# electron_v020.net
KiCad netlist of a schematic drawn in EAGLE
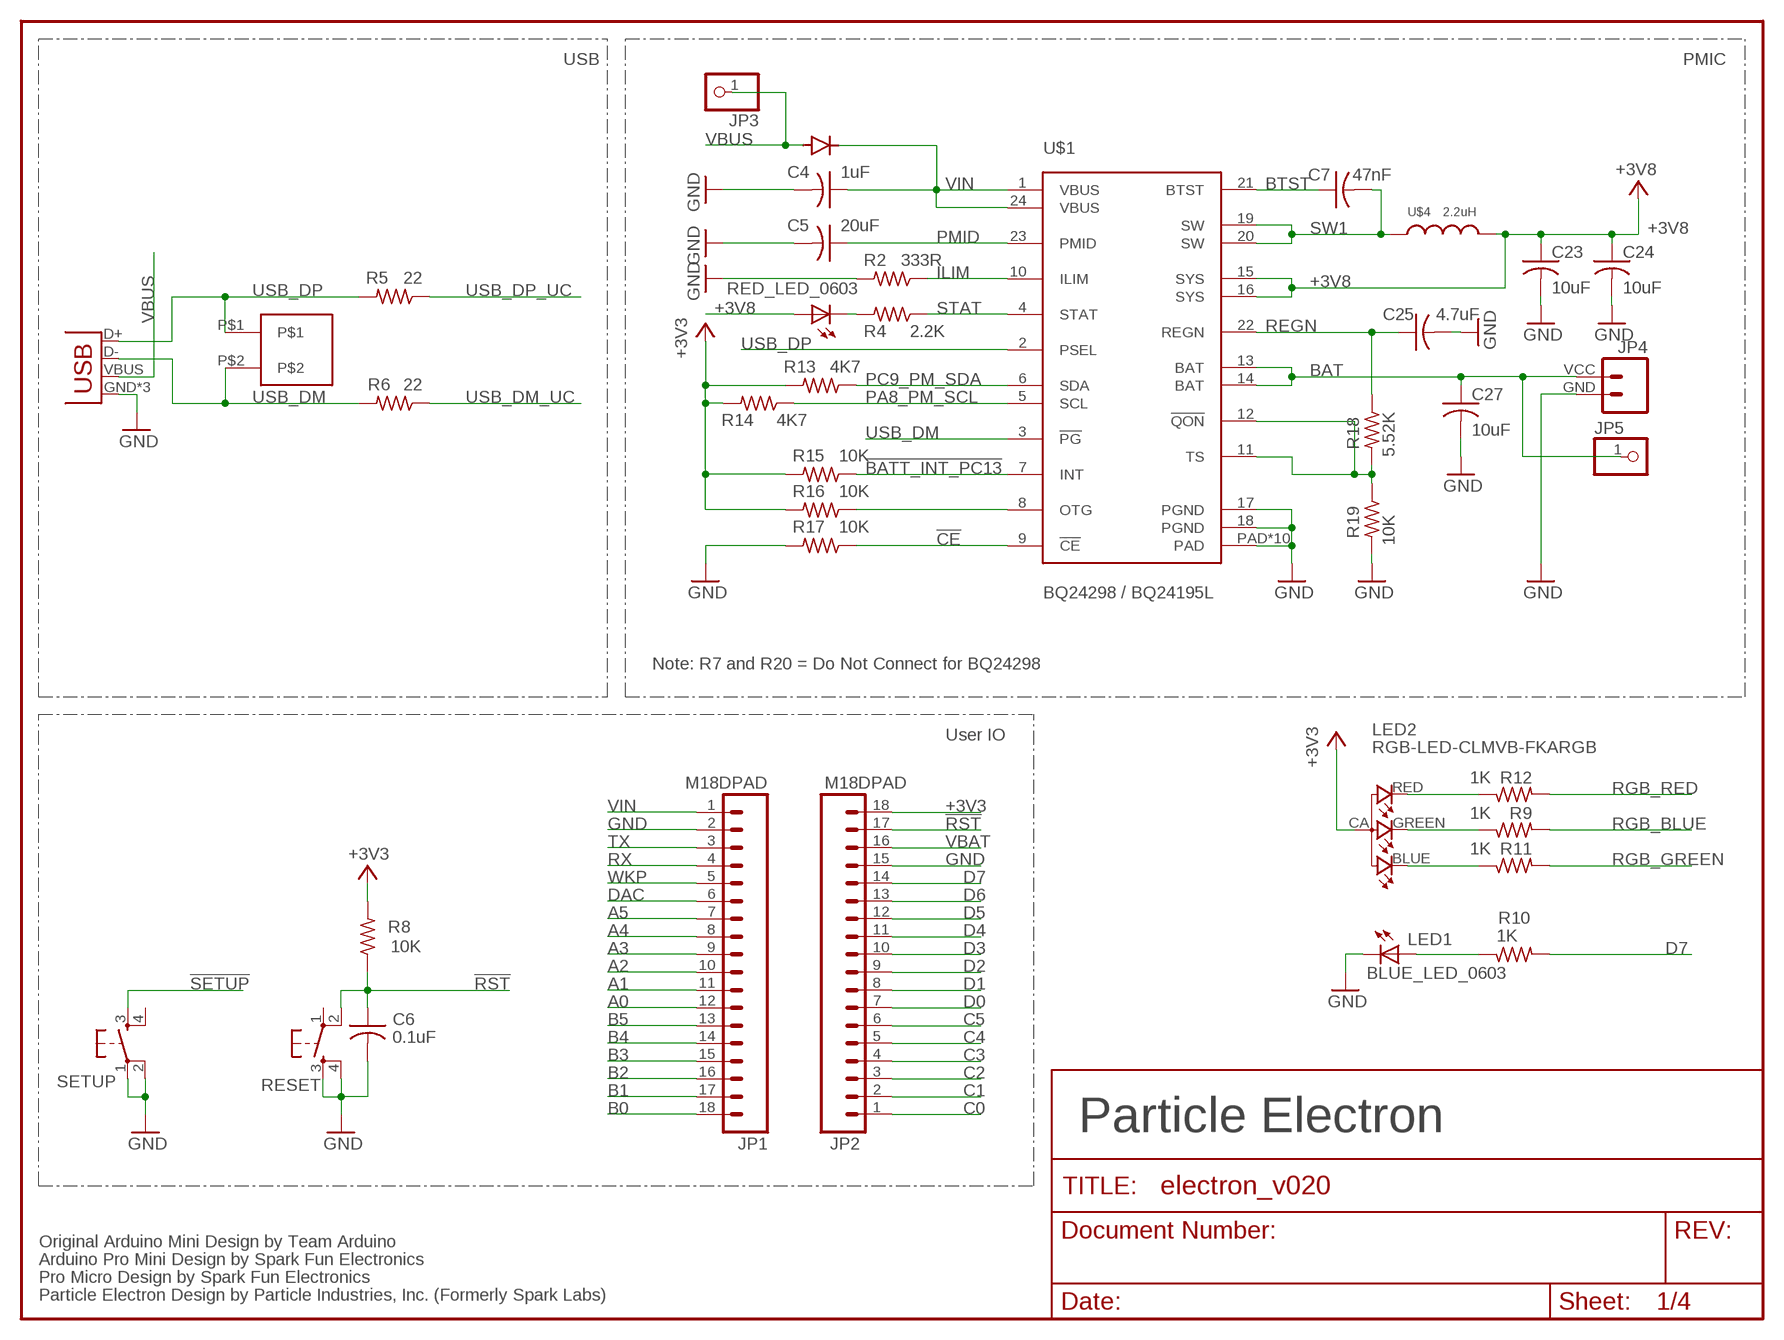
[diagram p0: schematic, sheet 1]
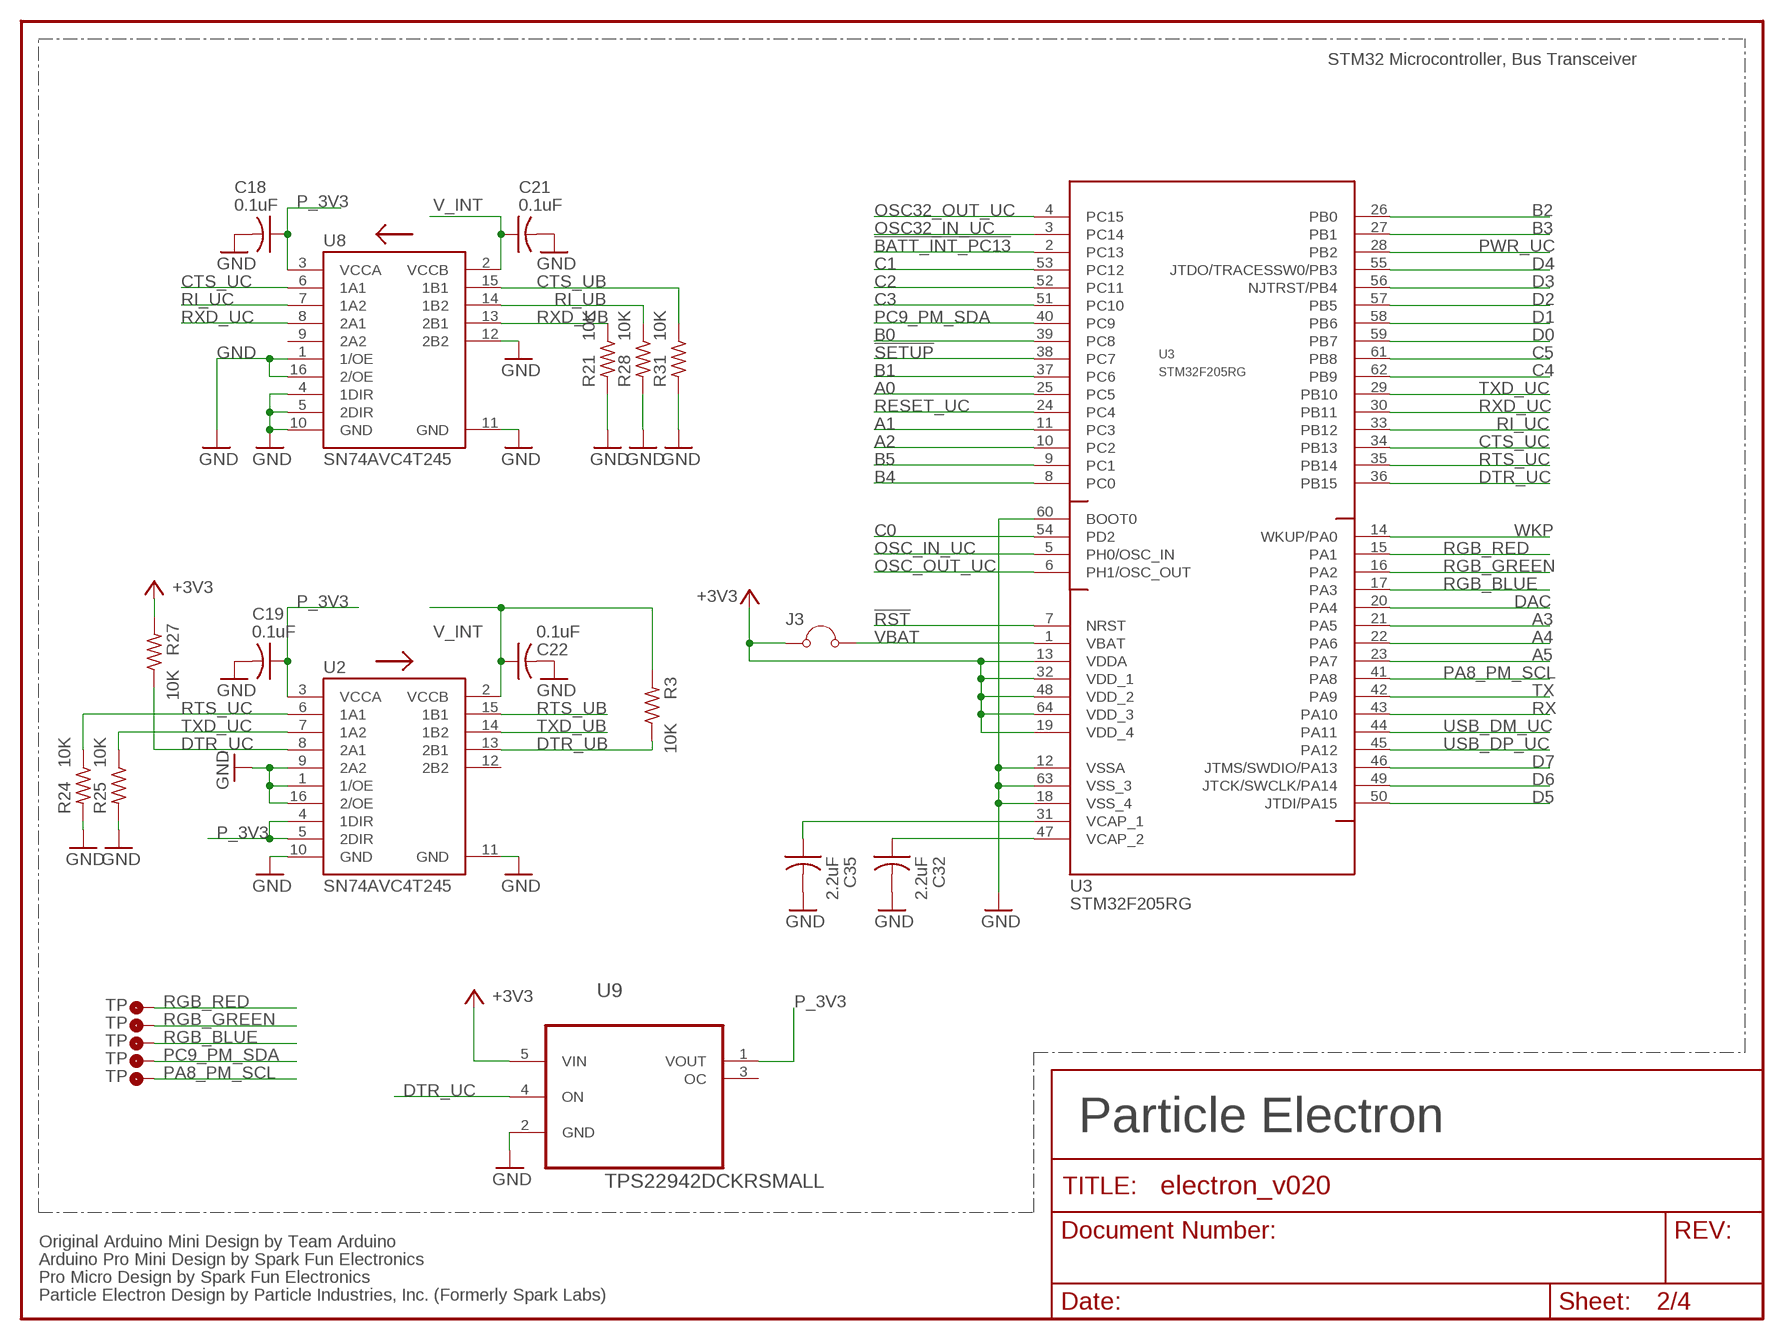
[diagram p1: schematic, sheet 2]
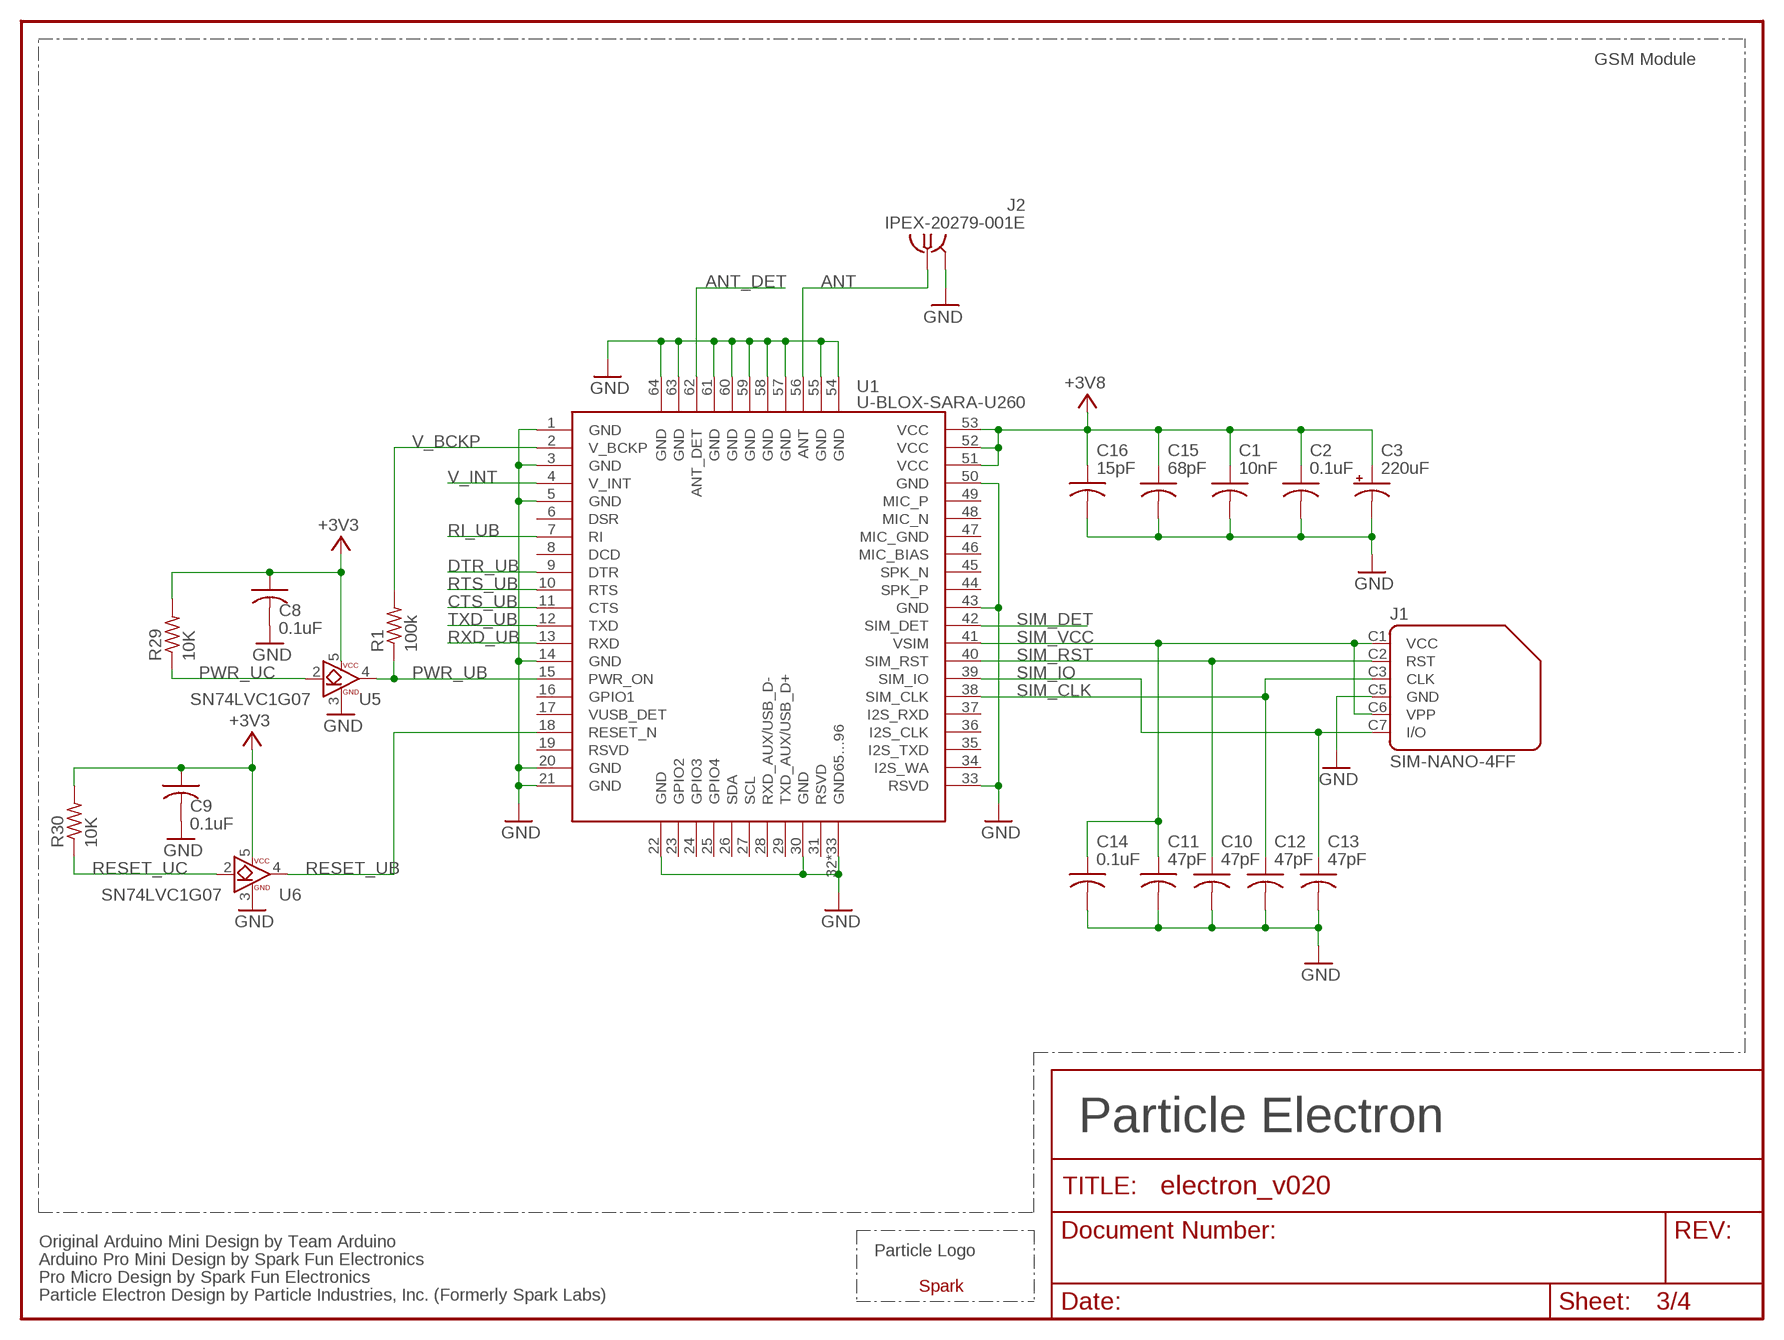
[diagram p2: schematic, sheet 3]
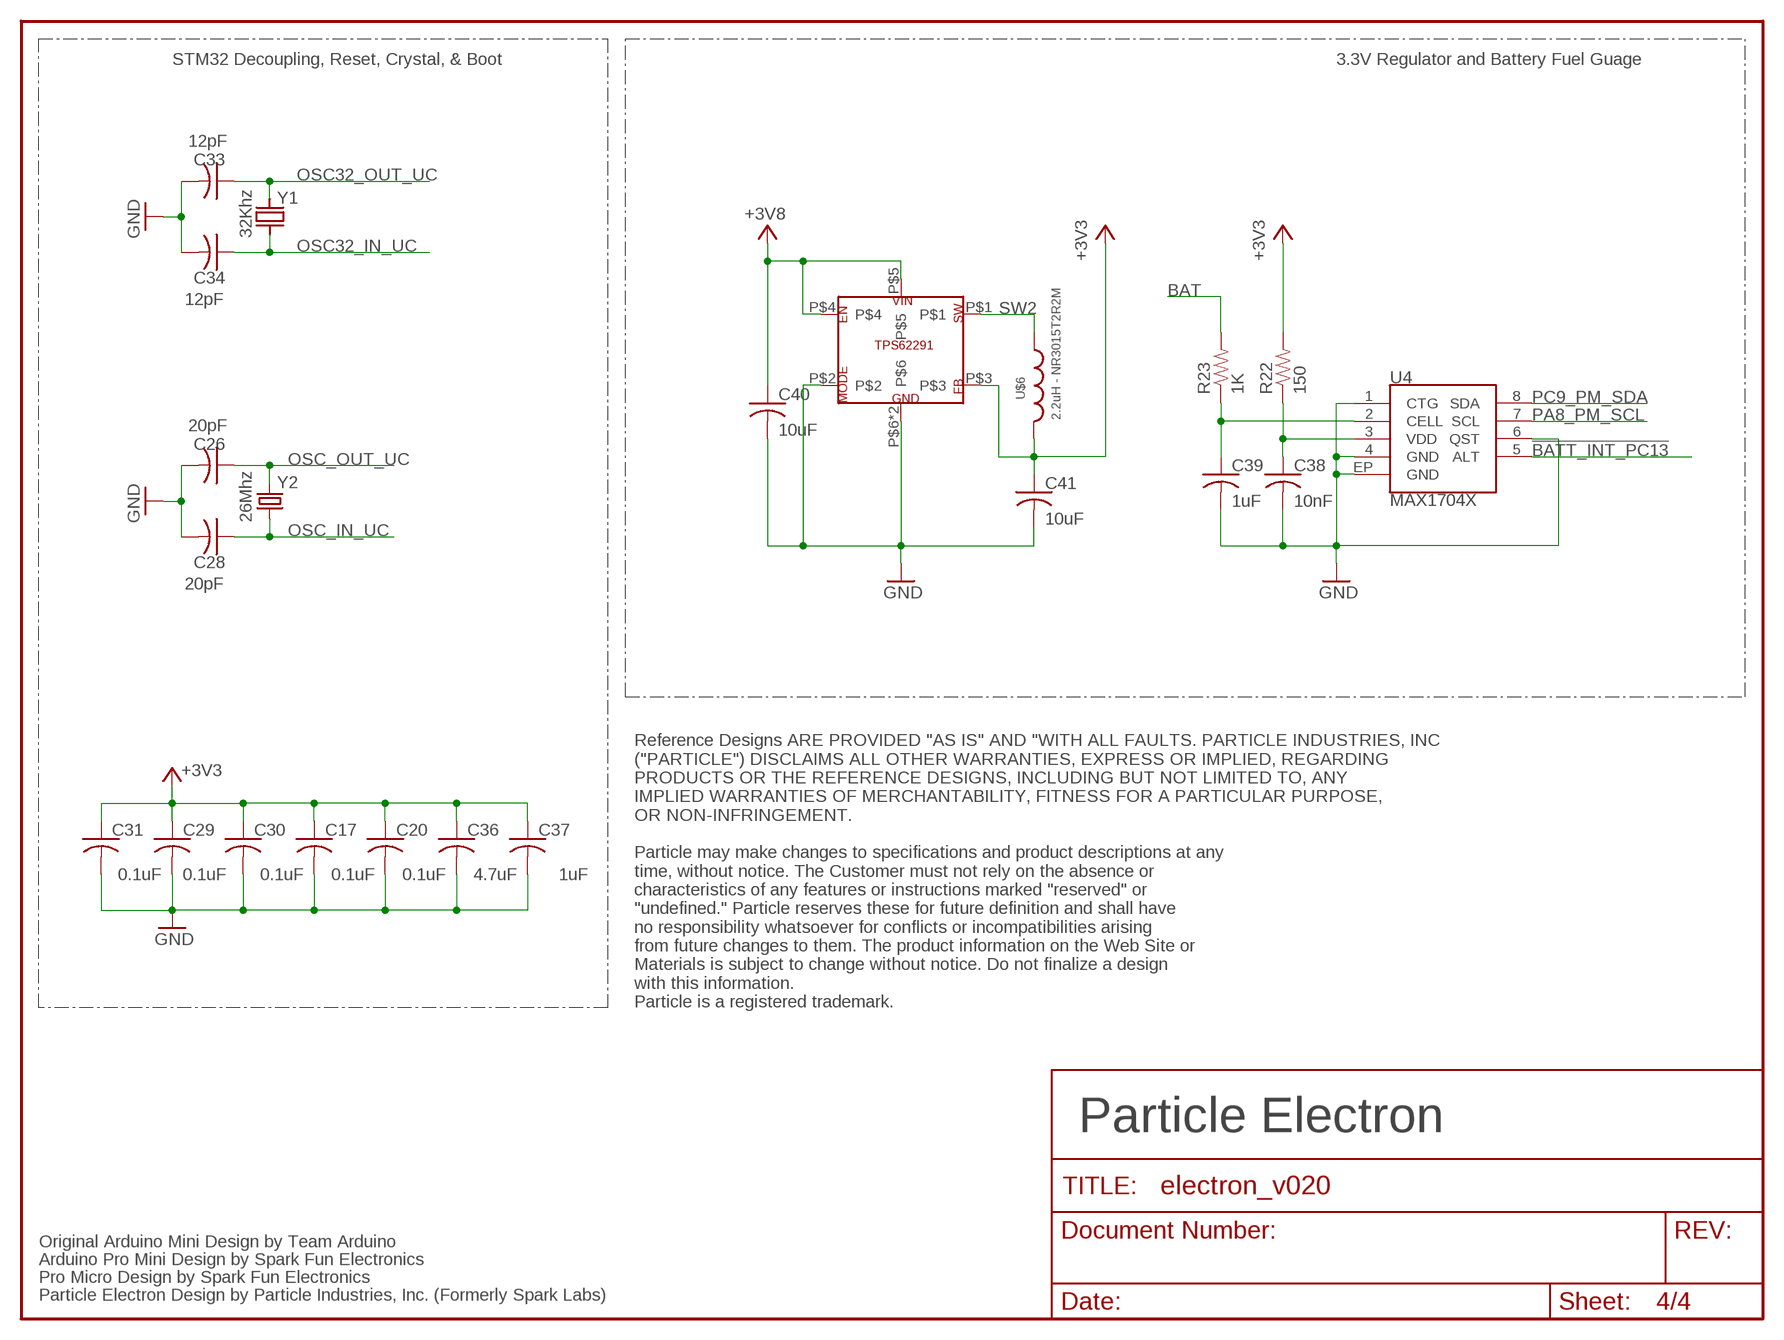
[diagram p3: schematic, sheet 4]

(export (version "E")
  (design (tool "Eeschema 10.0.6"))
  (components
    (comp (ref "C1")
      (value "10nF")
      (footprint "eagle-import:C0402_B")
      (libsource (lib "eagle-import") (part "C-US"))
    )
    (comp (ref "C2")
      (value "0.1uF")
      (footprint "eagle-import:C0402_B")
      (libsource (lib "eagle-import") (part "C-US"))
    )
    (comp (ref "C3")
      (value "220uF")
      (footprint "eagle-import:C_6032-28R")
      (libsource (lib "eagle-import") (part "CPOL-USC/6032-28R"))
    )
    (comp (ref "C8")
      (value "0.1uF")
      (footprint "eagle-import:C0402_B")
      (libsource (lib "eagle-import") (part "C-US"))
    )
    (comp (ref "C9")
      (value "0.1uF")
      (footprint "eagle-import:C0402_B")
      (libsource (lib "eagle-import") (part "C-US"))
    )
    (comp (ref "C10")
      (value "47pF")
      (footprint "eagle-import:C0402_B")
      (libsource (lib "eagle-import") (part "C-US"))
    )
    (comp (ref "C11")
      (value "47pF")
      (footprint "eagle-import:C0402_B")
      (libsource (lib "eagle-import") (part "C-US"))
    )
    (comp (ref "C12")
      (value "47pF")
      (footprint "eagle-import:C0402_B")
      (libsource (lib "eagle-import") (part "C-US"))
    )
    (comp (ref "C13")
      (value "47pF")
      (footprint "eagle-import:C0402_B")
      (libsource (lib "eagle-import") (part "C-US"))
    )
    (comp (ref "C14")
      (value "0.1uF")
      (footprint "eagle-import:C0402_B")
      (libsource (lib "eagle-import") (part "C-US"))
    )
    (comp (ref "C15")
      (value "68pF")
      (footprint "eagle-import:C0402_B")
      (libsource (lib "eagle-import") (part "C-US"))
    )
    (comp (ref "C16")
      (value "15pF")
      (footprint "eagle-import:C0402_B")
      (libsource (lib "eagle-import") (part "C-US"))
    )
    (comp (ref "J1")
      (value "SIM-NANO-4FF")
      (footprint "eagle-import:GCT-SIM8100")
      (libsource (lib "eagle-import") (part "SIM-NANO-4FF"))
    )
    (comp (ref "J2")
      (value "IPEX-20279-001E")
      (footprint "eagle-import:IPEX-20279-001E")
      (libsource (lib "eagle-import") (part "IPEX-20279-001E"))
    )
    (comp (ref "R1")
      (value "100k")
      (footprint "eagle-import:R0402_B")
      (libsource (lib "eagle-import") (part "R-US_"))
    )
    (comp (ref "R29")
      (value "10K")
      (footprint "eagle-import:R0402_B")
      (libsource (lib "eagle-import") (part "R-US_"))
    )
    (comp (ref "R30")
      (value "10K")
      (footprint "eagle-import:R0402_B")
      (libsource (lib "eagle-import") (part "R-US_"))
    )
    (comp (ref "U$2")
      (value "SPARK_LOGO2")
      (footprint "eagle-import:SPARK_LOGO2")
      (libsource (lib "eagle-import") (part "SPARK_LOGO2"))
    )
    (comp (ref "U1")
      (value "U-BLOX-SARA-U260")
      (footprint "eagle-import:U-BLOX-SARA-U2")
      (libsource (lib "eagle-import") (part "U-BLOX-SARA-U260"))
    )
    (comp (ref "U5")
      (value "SN74LVC1G07")
      (footprint "eagle-import:SC-70-5")
      (libsource (lib "eagle-import") (part "SN74LVC1G07"))
    )
    (comp (ref "U6")
      (value "SN74LVC1G07")
      (footprint "eagle-import:SC-70-5")
      (libsource (lib "eagle-import") (part "SN74LVC1G07"))
    )
    (comp (ref "BLUE_LED_0603")
      (value "LEDNOSILK")
      (footprint "eagle-import:LED-0603-NS")
      (libsource (lib "eagle-import") (part "LEDNOSILK"))
    )
    (comp (ref "C4")
      (value "1uF")
      (footprint "eagle-import:C0603_B")
      (libsource (lib "eagle-import") (part "C-US0603"))
    )
    (comp (ref "C5")
      (value "20uF")
      (footprint "eagle-import:C0603_B")
      (libsource (lib "eagle-import") (part "C-US0603"))
    )
    (comp (ref "C6")
      (value "0.1uF")
      (footprint "eagle-import:C0402_B")
      (libsource (lib "eagle-import") (part "C-US"))
    )
    (comp (ref "C7")
      (value "47nF")
      (footprint "eagle-import:C0402_B")
      (libsource (lib "eagle-import") (part "C-US"))
    )
    (comp (ref "C23")
      (value "10uF")
      (footprint "eagle-import:C0603_B")
      (libsource (lib "eagle-import") (part "C-US0603"))
    )
    (comp (ref "C24")
      (value "10uF")
      (footprint "eagle-import:C0603_B")
      (libsource (lib "eagle-import") (part "C-US0603"))
    )
    (comp (ref "C25")
      (value "4.7uF")
      (footprint "eagle-import:C0603_B")
      (libsource (lib "eagle-import") (part "C-US0603"))
    )
    (comp (ref "C27")
      (value "10uF")
      (footprint "eagle-import:C0603_B")
      (libsource (lib "eagle-import") (part "C-US0603"))
    )
    (comp (ref "JP1")
      (value "M18DPAD")
      (footprint "eagle-import:1X18-D-PADS")
      (libsource (lib "eagle-import") (part "M18DPAD"))
    )
    (comp (ref "JP2")
      (value "M18DPAD")
      (footprint "eagle-import:1X18-D-PADS")
      (libsource (lib "eagle-import") (part "M18DPAD"))
    )
    (comp (ref "JP3")
      (value "PINHD-1X1NOSILK")
      (footprint "eagle-import:1X01_NO_SILK")
      (libsource (lib "eagle-import") (part "PINHD-1X1NOSILK"))
    )
    (comp (ref "JP4")
      (value "M024UCON-15767")
      (footprint "eagle-import:JST-2-SMD-VERT")
      (libsource (lib "eagle-import") (part "M024UCON-15767"))
    )
    (comp (ref "JP5")
      (value "PINHD-1X1NOSILK")
      (footprint "eagle-import:1X01_NO_SILK")
      (libsource (lib "eagle-import") (part "PINHD-1X1NOSILK"))
    )
    (comp (ref "LED2")
      (value "RGB-LED-CLMVB-FKARGB")
      (footprint "eagle-import:PLCC4-2MM-RGB")
      (libsource (lib "eagle-import") (part "RGB-LED-CLMVB-FKARGB"))
    )
    (comp (ref "R2")
      (value "333R")
      (footprint "eagle-import:R0402_B")
      (libsource (lib "eagle-import") (part "R-US_"))
    )
    (comp (ref "R4")
      (value "2.2K")
      (footprint "eagle-import:R0402_B")
      (libsource (lib "eagle-import") (part "R-US_"))
    )
    (comp (ref "R5")
      (value "22")
      (footprint "eagle-import:R0402_B")
      (libsource (lib "eagle-import") (part "R-US_"))
    )
    (comp (ref "R6")
      (value "22")
      (footprint "eagle-import:R0402_B")
      (libsource (lib "eagle-import") (part "R-US_"))
    )
    (comp (ref "R8")
      (value "10K")
      (footprint "eagle-import:R0402_B")
      (libsource (lib "eagle-import") (part "R-US_"))
    )
    (comp (ref "R9")
      (value "1K")
      (footprint "eagle-import:R0402_B")
      (libsource (lib "eagle-import") (part "R-US_"))
    )
    (comp (ref "R10")
      (value "1K")
      (footprint "eagle-import:R0402_B")
      (libsource (lib "eagle-import") (part "R-US_"))
    )
    (comp (ref "R11")
      (value "1K")
      (footprint "eagle-import:R0402_B")
      (libsource (lib "eagle-import") (part "R-US_"))
    )
    (comp (ref "R12")
      (value "1K")
      (footprint "eagle-import:R0402_B")
      (libsource (lib "eagle-import") (part "R-US_"))
    )
    (comp (ref "R13")
      (value "4K7")
      (footprint "eagle-import:R0402_B")
      (libsource (lib "eagle-import") (part "R-US_"))
    )
    (comp (ref "R14")
      (value "4K7")
      (footprint "eagle-import:R0402_B")
      (libsource (lib "eagle-import") (part "R-US_"))
    )
    (comp (ref "R15")
      (value "10K")
      (footprint "eagle-import:R0402_B")
      (libsource (lib "eagle-import") (part "R-US_"))
    )
    (comp (ref "R16")
      (value "10K")
      (footprint "eagle-import:R0402_B")
      (libsource (lib "eagle-import") (part "R-US_"))
    )
    (comp (ref "R17")
      (value "10K")
      (footprint "eagle-import:R0402_B")
      (libsource (lib "eagle-import") (part "R-US_"))
    )
    (comp (ref "R18")
      (value "5.52K")
      (footprint "eagle-import:R0402_B")
      (libsource (lib "eagle-import") (part "R-US_"))
    )
    (comp (ref "R19")
      (value "10K")
      (footprint "eagle-import:R0402_B")
      (libsource (lib "eagle-import") (part "R-US_"))
    )
    (comp (ref "RED_LED_0603")
      (value "LED0603")
      (footprint "eagle-import:LED-0603")
      (libsource (lib "eagle-import") (part "LED0603"))
    )
    (comp (ref "RESET")
      (value "KMR211GLFS")
      (footprint "eagle-import:TACTILE_SWITCH_SMD")
      (libsource (lib "eagle-import") (part "TAC_SWITCHSMD"))
    )
    (comp (ref "SETUP")
      (value "KMR211GLFS")
      (footprint "eagle-import:TACTILE_SWITCH_SMD")
      (libsource (lib "eagle-import") (part "TAC_SWITCHSMD"))
    )
    (comp (ref "U$1")
      (value "BQ24298 / BQ24195L")
      (footprint "eagle-import:QFN24")
      (libsource (lib "eagle-import") (part "BQ24298RTWR"))
    )
    (comp (ref "U$3")
      (value "DIODE_NT")
      (footprint "eagle-import:DIODE-DO-220AA_NT(SMP)")
      (libsource (lib "eagle-import") (part "DIODE_NT"))
    )
    (comp (ref "U$4")
      (value "2.2uH")
      (footprint "eagle-import:4020TYPE_NT")
      (libsource (lib "eagle-import") (part "INDUCTOR_NT"))
    )
    (comp (ref "U$7")
      (value "M02_0.05_HEADER")
      (footprint "eagle-import:M02_0.05_HEADER")
      (libsource (lib "eagle-import") (part "M02_0.05_HEADER"))
    )
    (comp (ref "X1")
      (value "USB-MICROB")
      (footprint "eagle-import:USB-MICROB-SLOT-HOLE")
      (libsource (lib "eagle-import") (part "USBUSB-MICROB-SLOT-HOLE"))
    )
    (comp (ref "C17")
      (value "0.1uF")
      (footprint "eagle-import:C0402_B")
      (libsource (lib "eagle-import") (part "C-US"))
    )
    (comp (ref "C20")
      (value "0.1uF")
      (footprint "eagle-import:C0402_B")
      (libsource (lib "eagle-import") (part "C-US"))
    )
    (comp (ref "C26")
      (value "20pF")
      (footprint "eagle-import:C0402_B")
      (libsource (lib "eagle-import") (part "C-US"))
    )
    (comp (ref "C28")
      (value "20pF")
      (footprint "eagle-import:C0402_B")
      (libsource (lib "eagle-import") (part "C-US"))
    )
    (comp (ref "C29")
      (value "0.1uF")
      (footprint "eagle-import:C0402_B")
      (libsource (lib "eagle-import") (part "C-US"))
    )
    (comp (ref "C30")
      (value "0.1uF")
      (footprint "eagle-import:C0402_B")
      (libsource (lib "eagle-import") (part "C-US"))
    )
    (comp (ref "C31")
      (value "0.1uF")
      (footprint "eagle-import:C0402_B")
      (libsource (lib "eagle-import") (part "C-US"))
    )
    (comp (ref "C33")
      (value "12pF")
      (footprint "eagle-import:C0402_B")
      (libsource (lib "eagle-import") (part "C-US"))
    )
    (comp (ref "C34")
      (value "12pF")
      (footprint "eagle-import:C0402_B")
      (libsource (lib "eagle-import") (part "C-US"))
    )
    (comp (ref "C36")
      (value "4.7uF")
      (footprint "eagle-import:C0402_B")
      (libsource (lib "eagle-import") (part "C-US"))
    )
    (comp (ref "C37")
      (value "1uF")
      (footprint "eagle-import:C0402_B")
      (libsource (lib "eagle-import") (part "C-US"))
    )
    (comp (ref "C38")
      (value "10nF")
      (footprint "eagle-import:C0402_B")
      (libsource (lib "eagle-import") (part "C-US"))
    )
    (comp (ref "C39")
      (value "1uF")
      (footprint "eagle-import:C0402_B")
      (libsource (lib "eagle-import") (part "C-US"))
    )
    (comp (ref "C40")
      (value "10uF")
      (footprint "eagle-import:C0603_B")
      (libsource (lib "eagle-import") (part "C-US0603"))
    )
    (comp (ref "C41")
      (value "10uF")
      (footprint "eagle-import:C0603_B")
      (libsource (lib "eagle-import") (part "C-US0603"))
    )
    (comp (ref "R22")
      (value "150")
      (footprint "eagle-import:0603-RES")
      (libsource (lib "eagle-import") (part "RESISTOR0603-RES"))
    )
    (comp (ref "R23")
      (value "1K")
      (footprint "eagle-import:0603-RES")
      (libsource (lib "eagle-import") (part "RESISTOR0603-RES"))
    )
    (comp (ref "U$5")
      (value "TPS62291DRV")
      (footprint "eagle-import:S-PWSON-N6")
      (libsource (lib "eagle-import") (part "TPS62291DRV"))
    )
    (comp (ref "U$6")
      (value "2.2uH - NR3015T2R2M")
      (footprint "eagle-import:INDUCTOR-NR3015")
      (libsource (lib "eagle-import") (part "INDUCTORB"))
    )
    (comp (ref "U4")
      (value "MAX1704X")
      (footprint "eagle-import:TDFN-8")
      (libsource (lib "eagle-import") (part "MAX1704X"))
    )
    (comp (ref "Y1")
      (value "32Khz")
      (footprint "eagle-import:FC135")
      (libsource (lib "eagle-import") (part "Q_FC135"))
    )
    (comp (ref "Y2")
      (value "26Mhz")
      (footprint "eagle-import:CRYSTAL-SMD-5X3")
      (libsource (lib "eagle-import") (part "CRYSTAL5X3"))
    )
    (comp (ref "C18")
      (value "0.1uF")
      (footprint "eagle-import:C0402_B")
      (libsource (lib "eagle-import") (part "C-US"))
    )
    (comp (ref "C19")
      (value "0.1uF")
      (footprint "eagle-import:C0402_B")
      (libsource (lib "eagle-import") (part "C-US"))
    )
    (comp (ref "C21")
      (value "0.1uF")
      (footprint "eagle-import:C0402_B")
      (libsource (lib "eagle-import") (part "C-US"))
    )
    (comp (ref "C22")
      (value "0.1uF")
      (footprint "eagle-import:C0402_B")
      (libsource (lib "eagle-import") (part "C-US"))
    )
    (comp (ref "C32")
      (value "2.2uF")
      (footprint "eagle-import:C0402_B")
      (libsource (lib "eagle-import") (part "C-US"))
    )
    (comp (ref "C35")
      (value "2.2uF")
      (footprint "eagle-import:C0402_B")
      (libsource (lib "eagle-import") (part "C-US"))
    )
    (comp (ref "J3")
      (value "JUMPER_NC_SMD")
      (footprint "eagle-import:JUMPER_SMD_NC")
      (libsource (lib "eagle-import") (part "JUMPER_NC_SMD"))
    )
    (comp (ref "R3")
      (value "10K")
      (footprint "eagle-import:R0402_B")
      (libsource (lib "eagle-import") (part "R-US_"))
    )
    (comp (ref "R21")
      (value "10K")
      (footprint "eagle-import:R0402_B")
      (libsource (lib "eagle-import") (part "R-US_"))
    )
    (comp (ref "R24")
      (value "10K")
      (footprint "eagle-import:R0402_B")
      (libsource (lib "eagle-import") (part "R-US_"))
    )
    (comp (ref "R25")
      (value "10K")
      (footprint "eagle-import:R0402_B")
      (libsource (lib "eagle-import") (part "R-US_"))
    )
    (comp (ref "R27")
      (value "10K")
      (footprint "eagle-import:R0402_B")
      (libsource (lib "eagle-import") (part "R-US_"))
    )
    (comp (ref "R28")
      (value "10K")
      (footprint "eagle-import:R0402_B")
      (libsource (lib "eagle-import") (part "R-US_"))
    )
    (comp (ref "R31")
      (value "10K")
      (footprint "eagle-import:R0402_B")
      (libsource (lib "eagle-import") (part "R-US_"))
    )
    (comp (ref "U$8")
      (value "TP0")
      (footprint "eagle-import:TP30_BOT")
      (libsource (lib "eagle-import") (part "TP0"))
    )
    (comp (ref "U$9")
      (value "TP0")
      (footprint "eagle-import:TP30_BOT")
      (libsource (lib "eagle-import") (part "TP0"))
    )
    (comp (ref "U$11")
      (value "TP0")
      (footprint "eagle-import:TP30_BOT")
      (libsource (lib "eagle-import") (part "TP0"))
    )
    (comp (ref "U$12")
      (value "TP0")
      (footprint "eagle-import:TP30_BOT")
      (libsource (lib "eagle-import") (part "TP0"))
    )
    (comp (ref "U$13")
      (value "TP0")
      (footprint "eagle-import:TP30_BOT")
      (libsource (lib "eagle-import") (part "TP0"))
    )
    (comp (ref "U2")
      (value "SN74AVC4T245")
      (footprint "eagle-import:UFQFN-16")
      (libsource (lib "eagle-import") (part "SN74AVC4T245"))
    )
    (comp (ref "U3")
      (value "STM32F205RG")
      (footprint "eagle-import:LQFP64")
      (libsource (lib "eagle-import") (part "STM32F20XR"))
    )
    (comp (ref "U8")
      (value "SN74AVC4T245")
      (footprint "eagle-import:UFQFN-16")
      (libsource (lib "eagle-import") (part "SN74AVC4T245"))
    )
    (comp (ref "U9")
      (value "TPS22942DCKRSMALL")
      (footprint "eagle-import:SC70-5")
      (libsource (lib "eagle-import") (part "TPS22942DCKRSMALL"))
    )
  )
  (nets
    (net (code "1") (name "+3V3") (class "Default")
      (node (ref "C17") (pin "1") (pinfunction "1_1") (pintype "passive"))
      (node (ref "C20") (pin "1") (pinfunction "1_1") (pintype "passive"))
      (node (ref "C29") (pin "1") (pinfunction "1_1") (pintype "passive"))
      (node (ref "C30") (pin "1") (pinfunction "1_1") (pintype "passive"))
      (node (ref "C31") (pin "1") (pinfunction "1_1") (pintype "passive"))
      (node (ref "C36") (pin "1") (pinfunction "1_1") (pintype "passive"))
      (node (ref "C37") (pin "1") (pinfunction "1_1") (pintype "passive"))
      (node (ref "C41") (pin "1") (pinfunction "1_1") (pintype "passive"))
      (node (ref "C8") (pin "1") (pinfunction "1_1") (pintype "passive"))
      (node (ref "C9") (pin "1") (pinfunction "1_1") (pintype "passive"))
      (node (ref "J3") (pin "1") (pinfunction "1_1") (pintype "bidirectional"))
      (node (ref "JP2") (pin "18") (pinfunction "18_18") (pintype "passive"))
      (node (ref "LED2") (pin "CA") (pinfunction "1_CA") (pintype "passive"))
      (node (ref "R13") (pin "2") (pinfunction "2_2") (pintype "passive"))
      (node (ref "R14") (pin "2") (pinfunction "2_2") (pintype "passive"))
      (node (ref "R15") (pin "2") (pinfunction "2_2") (pintype "passive"))
      (node (ref "R16") (pin "2") (pinfunction "2_2") (pintype "passive"))
      (node (ref "R22") (pin "2") (pinfunction "2_2") (pintype "passive"))
      (node (ref "R27") (pin "2") (pinfunction "2_2") (pintype "passive"))
      (node (ref "R29") (pin "2") (pinfunction "2_2") (pintype "passive"))
      (node (ref "R30") (pin "2") (pinfunction "2_2") (pintype "passive"))
      (node (ref "R8") (pin "2") (pinfunction "2_2") (pintype "passive"))
      (node (ref "U$5") (pin "P$3") (pinfunction "P$3_P$3") (pintype "bidirectional"))
      (node (ref "U$6") (pin "2") (pinfunction "2_2") (pintype "passive"))
      (node (ref "U3") (pin "13") (pinfunction "VDDA_13") (pintype "power_in"))
      (node (ref "U3") (pin "19") (pinfunction "VDD_4_19") (pintype "power_in"))
      (node (ref "U3") (pin "32") (pinfunction "VDD_1_32") (pintype "power_in"))
      (node (ref "U3") (pin "48") (pinfunction "VDD_2_48") (pintype "power_in"))
      (node (ref "U3") (pin "64") (pinfunction "VDD_3_64") (pintype "power_in"))
      (node (ref "U5") (pin "5") (pinfunction "VCC_5") (pintype "bidirectional"))
      (node (ref "U6") (pin "5") (pinfunction "VCC_5") (pintype "bidirectional"))
      (node (ref "U9") (pin "5") (pinfunction "VIN_5") (pintype "power_in"))
    )
    (net (code "2") (name "+3V8") (class "Default")
      (node (ref "C1") (pin "1") (pinfunction "1_1") (pintype "passive"))
      (node (ref "C15") (pin "1") (pinfunction "1_1") (pintype "passive"))
      (node (ref "C16") (pin "1") (pinfunction "1_1") (pintype "passive"))
      (node (ref "C2") (pin "1") (pinfunction "1_1") (pintype "passive"))
      (node (ref "C23") (pin "1") (pinfunction "1_1") (pintype "passive"))
      (node (ref "C24") (pin "1") (pinfunction "1_1") (pintype "passive"))
      (node (ref "C3") (pin "+") (pinfunction "+_+") (pintype "passive"))
      (node (ref "C40") (pin "1") (pinfunction "1_1") (pintype "passive"))
      (node (ref "RED_LED_0603") (pin "A") (pinfunction "A_A") (pintype "passive"))
      (node (ref "U$1") (pin "15") (pinfunction "SYS_15") (pintype "power_in"))
      (node (ref "U$1") (pin "16") (pinfunction "SYS_16") (pintype "power_in"))
      (node (ref "U$4") (pin "P$2") (pinfunction "2_P$2") (pintype "passive"))
      (node (ref "U$5") (pin "P$4") (pinfunction "P$4_P$4") (pintype "bidirectional"))
      (node (ref "U$5") (pin "P$5") (pinfunction "P$5_P$5") (pintype "bidirectional"))
      (node (ref "U1") (pin "51") (pinfunction "VCC_51") (pintype "bidirectional"))
      (node (ref "U1") (pin "52") (pinfunction "VCC_52") (pintype "bidirectional"))
      (node (ref "U1") (pin "53") (pinfunction "VCC_53") (pintype "bidirectional"))
    )
    (net (code "3") (name "A0") (class "Default")
      (node (ref "JP1") (pin "12") (pinfunction "12_12") (pintype "passive"))
      (node (ref "U3") (pin "25") (pinfunction "PC5_25") (pintype "bidirectional"))
    )
    (net (code "4") (name "A1") (class "Default")
      (node (ref "JP1") (pin "11") (pinfunction "11_11") (pintype "passive"))
      (node (ref "U3") (pin "11") (pinfunction "PC3_11") (pintype "bidirectional"))
    )
    (net (code "5") (name "A2") (class "Default")
      (node (ref "JP1") (pin "10") (pinfunction "10_10") (pintype "passive"))
      (node (ref "U3") (pin "10") (pinfunction "PC2_10") (pintype "bidirectional"))
    )
    (net (code "6") (name "A3") (class "Default")
      (node (ref "JP1") (pin "9") (pinfunction "9_9") (pintype "passive"))
      (node (ref "U3") (pin "21") (pinfunction "PA5_21") (pintype "bidirectional"))
    )
    (net (code "7") (name "A4") (class "Default")
      (node (ref "JP1") (pin "8") (pinfunction "8_8") (pintype "passive"))
      (node (ref "U3") (pin "22") (pinfunction "PA6_22") (pintype "bidirectional"))
    )
    (net (code "8") (name "A5") (class "Default")
      (node (ref "JP1") (pin "7") (pinfunction "7_7") (pintype "passive"))
      (node (ref "U3") (pin "23") (pinfunction "PA7_23") (pintype "bidirectional"))
    )
    (net (code "9") (name "ANT") (class "Default")
      (node (ref "J2") (pin "1") (pinfunction "1_1") (pintype "passive"))
      (node (ref "U1") (pin "56") (pinfunction "ANT_56") (pintype "bidirectional"))
    )
    (net (code "10") (name "ANT_DET") (class "Default")
      (node (ref "U1") (pin "62") (pinfunction "ANT_DET_62") (pintype "bidirectional"))
    )
    (net (code "11") (name "B0") (class "Default")
      (node (ref "JP1") (pin "18") (pinfunction "18_18") (pintype "passive"))
      (node (ref "U3") (pin "39") (pinfunction "PC8_39") (pintype "bidirectional"))
    )
    (net (code "12") (name "B1") (class "Default")
      (node (ref "JP1") (pin "17") (pinfunction "17_17") (pintype "passive"))
      (node (ref "U3") (pin "37") (pinfunction "PC6_37") (pintype "bidirectional"))
    )
    (net (code "13") (name "B2") (class "Default")
      (node (ref "JP1") (pin "16") (pinfunction "16_16") (pintype "passive"))
      (node (ref "U3") (pin "26") (pinfunction "PB0_26") (pintype "bidirectional"))
    )
    (net (code "14") (name "B3") (class "Default")
      (node (ref "JP1") (pin "15") (pinfunction "15_15") (pintype "passive"))
      (node (ref "U3") (pin "27") (pinfunction "PB1_27") (pintype "bidirectional"))
    )
    (net (code "15") (name "B4") (class "Default")
      (node (ref "JP1") (pin "14") (pinfunction "14_14") (pintype "passive"))
      (node (ref "U3") (pin "8") (pinfunction "PC0_8") (pintype "bidirectional"))
    )
    (net (code "16") (name "B5") (class "Default")
      (node (ref "JP1") (pin "13") (pinfunction "13_13") (pintype "passive"))
      (node (ref "U3") (pin "9") (pinfunction "PC1_9") (pintype "bidirectional"))
    )
    (net (code "17") (name "BAT") (class "Default")
      (node (ref "C27") (pin "1") (pinfunction "1_1") (pintype "passive"))
      (node (ref "JP4") (pin "VCC") (pinfunction "2_VCC") (pintype "passive"))
      (node (ref "JP5") (pin "1") (pinfunction "1_1") (pintype "passive"))
      (node (ref "R23") (pin "2") (pinfunction "2_2") (pintype "passive"))
      (node (ref "U$1") (pin "13") (pinfunction "BAT_13") (pintype "passive"))
      (node (ref "U$1") (pin "14") (pinfunction "BAT_14") (pintype "power_in"))
    )
    (net (code "18") (name "BTST") (class "Default")
      (node (ref "C7") (pin "1") (pinfunction "1_1") (pintype "passive"))
      (node (ref "U$1") (pin "21") (pinfunction "BTST_21") (pintype "bidirectional"))
    )
    (net (code "19") (name "C0") (class "Default")
      (node (ref "JP2") (pin "1") (pinfunction "1_1") (pintype "passive"))
      (node (ref "U3") (pin "54") (pinfunction "PD2_54") (pintype "bidirectional"))
    )
    (net (code "20") (name "C1") (class "Default")
      (node (ref "JP2") (pin "2") (pinfunction "2_2") (pintype "passive"))
      (node (ref "U3") (pin "53") (pinfunction "PC12_53") (pintype "bidirectional"))
    )
    (net (code "21") (name "C2") (class "Default")
      (node (ref "JP2") (pin "3") (pinfunction "3_3") (pintype "passive"))
      (node (ref "U3") (pin "52") (pinfunction "PC11_52") (pintype "bidirectional"))
    )
    (net (code "22") (name "C3") (class "Default")
      (node (ref "JP2") (pin "4") (pinfunction "4_4") (pintype "passive"))
      (node (ref "U3") (pin "51") (pinfunction "PC10_51") (pintype "bidirectional"))
    )
    (net (code "23") (name "C4") (class "Default")
      (node (ref "JP2") (pin "5") (pinfunction "5_5") (pintype "passive"))
      (node (ref "U3") (pin "62") (pinfunction "PB9_62") (pintype "bidirectional"))
    )
    (net (code "24") (name "C5") (class "Default")
      (node (ref "JP2") (pin "6") (pinfunction "6_6") (pintype "passive"))
      (node (ref "U3") (pin "61") (pinfunction "PB8_61") (pintype "bidirectional"))
    )
    (net (code "25") (name "CTS_UB") (class "Default")
      (node (ref "R31") (pin "1") (pinfunction "1_1") (pintype "passive"))
      (node (ref "U1") (pin "11") (pinfunction "CTS_11") (pintype "bidirectional"))
      (node (ref "U8") (pin "15") (pinfunction "1B1_15") (pintype "bidirectional"))
    )
    (net (code "26") (name "CTS_UC") (class "Default")
      (node (ref "U3") (pin "34") (pinfunction "PB13_34") (pintype "bidirectional"))
      (node (ref "U8") (pin "6") (pinfunction "1A1_6") (pintype "bidirectional"))
    )
    (net (code "27") (name "D0") (class "Default")
      (node (ref "JP2") (pin "7") (pinfunction "7_7") (pintype "passive"))
      (node (ref "U3") (pin "59") (pinfunction "PB7_59") (pintype "bidirectional"))
    )
    (net (code "28") (name "D1") (class "Default")
      (node (ref "JP2") (pin "8") (pinfunction "8_8") (pintype "passive"))
      (node (ref "U3") (pin "58") (pinfunction "PB6_58") (pintype "bidirectional"))
    )
    (net (code "29") (name "D2") (class "Default")
      (node (ref "JP2") (pin "9") (pinfunction "9_9") (pintype "passive"))
      (node (ref "U3") (pin "57") (pinfunction "PB5_57") (pintype "bidirectional"))
    )
    (net (code "30") (name "D3") (class "Default")
      (node (ref "JP2") (pin "10") (pinfunction "10_10") (pintype "passive"))
      (node (ref "U3") (pin "56") (pinfunction "NJTRST/PB4_56") (pintype "bidirectional"))
    )
    (net (code "31") (name "D4") (class "Default")
      (node (ref "JP2") (pin "11") (pinfunction "11_11") (pintype "passive"))
      (node (ref "U3") (pin "55") (pinfunction "JTDO/TRACESSW0/PB3_55") (pintype "bidirectional"))
    )
    (net (code "32") (name "D5") (class "Default")
      (node (ref "JP2") (pin "12") (pinfunction "12_12") (pintype "passive"))
      (node (ref "U3") (pin "50") (pinfunction "JTDI/PA15_50") (pintype "bidirectional"))
    )
    (net (code "33") (name "D6") (class "Default")
      (node (ref "JP2") (pin "13") (pinfunction "13_13") (pintype "passive"))
      (node (ref "U3") (pin "49") (pinfunction "JTCK/SWCLK/PA14_49") (pintype "bidirectional"))
    )
    (net (code "34") (name "D7") (class "Default")
      (node (ref "JP2") (pin "14") (pinfunction "14_14") (pintype "passive"))
      (node (ref "R10") (pin "2") (pinfunction "2_2") (pintype "passive"))
      (node (ref "U3") (pin "46") (pinfunction "JTMS/SWDIO/PA13_46") (pintype "bidirectional"))
    )
    (net (code "35") (name "DAC") (class "Default")
      (node (ref "JP1") (pin "6") (pinfunction "6_6") (pintype "passive"))
      (node (ref "U3") (pin "20") (pinfunction "PA4_20") (pintype "bidirectional"))
    )
    (net (code "36") (name "DTR_UB") (class "Default")
      (node (ref "R3") (pin "1") (pinfunction "1_1") (pintype "passive"))
      (node (ref "U1") (pin "9") (pinfunction "DTR_9") (pintype "bidirectional"))
      (node (ref "U2") (pin "13") (pinfunction "2B1_13") (pintype "bidirectional"))
    )
    (net (code "37") (name "DTR_UC") (class "Default")
      (node (ref "R27") (pin "1") (pinfunction "1_1") (pintype "passive"))
      (node (ref "U2") (pin "8") (pinfunction "2A1_8") (pintype "bidirectional"))
      (node (ref "U3") (pin "36") (pinfunction "PB15_36") (pintype "bidirectional"))
      (node (ref "U9") (pin "4") (pinfunction "ON_4") (pintype "input"))
    )
    (net (code "38") (name "GND") (class "Default")
      (node (ref "BLUE_LED_0603") (pin "C") (pinfunction "C_C") (pintype "passive"))
      (node (ref "C1") (pin "2") (pinfunction "2_2") (pintype "passive"))
      (node (ref "C10") (pin "2") (pinfunction "2_2") (pintype "passive"))
      (node (ref "C11") (pin "2") (pinfunction "2_2") (pintype "passive"))
      (node (ref "C12") (pin "2") (pinfunction "2_2") (pintype "passive"))
      (node (ref "C13") (pin "2") (pinfunction "2_2") (pintype "passive"))
      (node (ref "C14") (pin "2") (pinfunction "2_2") (pintype "passive"))
      (node (ref "C15") (pin "2") (pinfunction "2_2") (pintype "passive"))
      (node (ref "C16") (pin "2") (pinfunction "2_2") (pintype "passive"))
      (node (ref "C17") (pin "2") (pinfunction "2_2") (pintype "passive"))
      (node (ref "C18") (pin "2") (pinfunction "2_2") (pintype "passive"))
      (node (ref "C19") (pin "2") (pinfunction "2_2") (pintype "passive"))
      (node (ref "C2") (pin "2") (pinfunction "2_2") (pintype "passive"))
      (node (ref "C20") (pin "2") (pinfunction "2_2") (pintype "passive"))
      (node (ref "C21") (pin "2") (pinfunction "2_2") (pintype "passive"))
      (node (ref "C22") (pin "2") (pinfunction "2_2") (pintype "passive"))
      (node (ref "C23") (pin "2") (pinfunction "2_2") (pintype "passive"))
      (node (ref "C24") (pin "2") (pinfunction "2_2") (pintype "passive"))
      (node (ref "C25") (pin "2") (pinfunction "2_2") (pintype "passive"))
      (node (ref "C26") (pin "2") (pinfunction "2_2") (pintype "passive"))
      (node (ref "C27") (pin "2") (pinfunction "2_2") (pintype "passive"))
      (node (ref "C28") (pin "2") (pinfunction "2_2") (pintype "passive"))
      (node (ref "C29") (pin "2") (pinfunction "2_2") (pintype "passive"))
      (node (ref "C3") (pin "-") (pinfunction "-_-") (pintype "passive"))
      (node (ref "C30") (pin "2") (pinfunction "2_2") (pintype "passive"))
      (node (ref "C31") (pin "2") (pinfunction "2_2") (pintype "passive"))
      (node (ref "C32") (pin "2") (pinfunction "2_2") (pintype "passive"))
      (node (ref "C33") (pin "2") (pinfunction "2_2") (pintype "passive"))
      (node (ref "C34") (pin "2") (pinfunction "2_2") (pintype "passive"))
      (node (ref "C35") (pin "2") (pinfunction "2_2") (pintype "passive"))
      (node (ref "C36") (pin "2") (pinfunction "2_2") (pintype "passive"))
      (node (ref "C37") (pin "2") (pinfunction "2_2") (pintype "passive"))
      (node (ref "C38") (pin "2") (pinfunction "2_2") (pintype "passive"))
      (node (ref "C39") (pin "2") (pinfunction "2_2") (pintype "passive"))
      (node (ref "C4") (pin "2") (pinfunction "2_2") (pintype "passive"))
      (node (ref "C40") (pin "2") (pinfunction "2_2") (pintype "passive"))
      (node (ref "C41") (pin "2") (pinfunction "2_2") (pintype "passive"))
      (node (ref "C5") (pin "2") (pinfunction "2_2") (pintype "passive"))
      (node (ref "C6") (pin "2") (pinfunction "2_2") (pintype "passive"))
      (node (ref "C8") (pin "2") (pinfunction "2_2") (pintype "passive"))
      (node (ref "C9") (pin "2") (pinfunction "2_2") (pintype "passive"))
      (node (ref "J1") (pin "C5") (pinfunction "GND_C5") (pintype "passive"))
      (node (ref "J2") (pin "2@1") (pinfunction "GND_2@1") (pintype "passive"))
      (node (ref "J2") (pin "2@2") (pinfunction "GND_2@2") (pintype "passive"))
      (node (ref "JP1") (pin "2") (pinfunction "2_2") (pintype "passive"))
      (node (ref "JP2") (pin "15") (pinfunction "15_15") (pintype "passive"))
      (node (ref "JP4") (pin "GND") (pinfunction "1_GND") (pintype "passive"))
      (node (ref "R17") (pin "2") (pinfunction "2_2") (pintype "passive"))
      (node (ref "R19") (pin "2") (pinfunction "2_2") (pintype "passive"))
      (node (ref "R2") (pin "2") (pinfunction "2_2") (pintype "passive"))
      (node (ref "R21") (pin "2") (pinfunction "2_2") (pintype "passive"))
      (node (ref "R24") (pin "2") (pinfunction "2_2") (pintype "passive"))
      (node (ref "R25") (pin "2") (pinfunction "2_2") (pintype "passive"))
      (node (ref "R28") (pin "2") (pinfunction "2_2") (pintype "passive"))
      (node (ref "R31") (pin "2") (pinfunction "2_2") (pintype "passive"))
      (node (ref "RESET") (pin "3") (pinfunction "3_3") (pintype "passive"))
      (node (ref "RESET") (pin "4") (pinfunction "4_4") (pintype "passive"))
      (node (ref "SETUP") (pin "1") (pinfunction "1_1") (pintype "passive"))
      (node (ref "SETUP") (pin "2") (pinfunction "2_2") (pintype "passive"))
      (node (ref "U$1") (pin "17") (pinfunction "PGND_17") (pintype "passive"))
      (node (ref "U$1") (pin "18") (pinfunction "PGND_18") (pintype "passive"))
      (node (ref "U$1") (pin "PAD") (pinfunction "PAD_PAD") (pintype "power_in"))
      (node (ref "U$1") (pin "PAD@1") (pinfunction "PAD_PAD@1") (pintype "power_in"))
      (node (ref "U$1") (pin "PAD@2") (pinfunction "PAD_PAD@2") (pintype "power_in"))
      (node (ref "U$1") (pin "PAD@3") (pinfunction "PAD_PAD@3") (pintype "power_in"))
      (node (ref "U$1") (pin "PAD@4") (pinfunction "PAD_PAD@4") (pintype "power_in"))
      (node (ref "U$1") (pin "PAD@5") (pinfunction "PAD_PAD@5") (pintype "power_in"))
      (node (ref "U$1") (pin "PAD@6") (pinfunction "PAD_PAD@6") (pintype "power_in"))
      (node (ref "U$1") (pin "PAD@7") (pinfunction "PAD_PAD@7") (pintype "power_in"))
      (node (ref "U$1") (pin "PAD@8") (pinfunction "PAD_PAD@8") (pintype "power_in"))
      (node (ref "U$1") (pin "PAD@9") (pinfunction "PAD_PAD@9") (pintype "power_in"))
      (node (ref "U$5") (pin "P$2") (pinfunction "P$2_P$2") (pintype "bidirectional"))
      (node (ref "U$5") (pin "P$6") (pinfunction "P$6_P$6") (pintype "bidirectional"))
      (node (ref "U$5") (pin "TP") (pinfunction "P$6_TP") (pintype "bidirectional"))
      (node (ref "U1") (pin "1") (pinfunction "GND_1") (pintype "bidirectional"))
      (node (ref "U1") (pin "14") (pinfunction "GND_14") (pintype "bidirectional"))
      (node (ref "U1") (pin "20") (pinfunction "GND_20") (pintype "bidirectional"))
      (node (ref "U1") (pin "21") (pinfunction "GND_21") (pintype "bidirectional"))
      (node (ref "U1") (pin "22") (pinfunction "GND_22") (pintype "bidirectional"))
      (node (ref "U1") (pin "3") (pinfunction "GND_3") (pintype "bidirectional"))
      (node (ref "U1") (pin "30") (pinfunction "GND_30") (pintype "bidirectional"))
      (node (ref "U1") (pin "32") (pinfunction "GND65...96_32") (pintype "bidirectional"))
      (node (ref "U1") (pin "33") (pinfunction "RSVD_33") (pintype "bidirectional"))
      (node (ref "U1") (pin "43") (pinfunction "GND_43") (pintype "bidirectional"))
      (node (ref "U1") (pin "5") (pinfunction "GND_5") (pintype "bidirectional"))
      (node (ref "U1") (pin "50") (pinfunction "GND_50") (pintype "bidirectional"))
      (node (ref "U1") (pin "54") (pinfunction "GND_54") (pintype "bidirectional"))
      (node (ref "U1") (pin "55") (pinfunction "GND_55") (pintype "bidirectional"))
      (node (ref "U1") (pin "57") (pinfunction "GND_57") (pintype "bidirectional"))
      (node (ref "U1") (pin "58") (pinfunction "GND_58") (pintype "bidirectional"))
      (node (ref "U1") (pin "59") (pinfunction "GND_59") (pintype "bidirectional"))
      (node (ref "U1") (pin "60") (pinfunction "GND_60") (pintype "bidirectional"))
      (node (ref "U1") (pin "61") (pinfunction "GND_61") (pintype "bidirectional"))
      (node (ref "U1") (pin "63") (pinfunction "GND_63") (pintype "bidirectional"))
      (node (ref "U1") (pin "64") (pinfunction "GND_64") (pintype "bidirectional"))
      (node (ref "U1") (pin "65") (pinfunction "GND65...96_65") (pintype "bidirectional"))
      (node (ref "U1") (pin "66") (pinfunction "GND65...96_66") (pintype "bidirectional"))
      (node (ref "U1") (pin "67") (pinfunction "GND65...96_67") (pintype "bidirectional"))
      (node (ref "U1") (pin "68") (pinfunction "GND65...96_68") (pintype "bidirectional"))
      (node (ref "U1") (pin "69") (pinfunction "GND65...96_69") (pintype "bidirectional"))
      (node (ref "U1") (pin "70") (pinfunction "GND65...96_70") (pintype "bidirectional"))
      (node (ref "U1") (pin "71") (pinfunction "GND65...96_71") (pintype "bidirectional"))
      (node (ref "U1") (pin "72") (pinfunction "GND65...96_72") (pintype "bidirectional"))
      (node (ref "U1") (pin "73") (pinfunction "GND65...96_73") (pintype "bidirectional"))
      (node (ref "U1") (pin "74") (pinfunction "GND65...96_74") (pintype "bidirectional"))
      (node (ref "U1") (pin "75") (pinfunction "GND65...96_75") (pintype "bidirectional"))
      (node (ref "U1") (pin "76") (pinfunction "GND65...96_76") (pintype "bidirectional"))
      (node (ref "U1") (pin "77") (pinfunction "GND65...96_77") (pintype "bidirectional"))
      (node (ref "U1") (pin "78") (pinfunction "GND65...96_78") (pintype "bidirectional"))
      (node (ref "U1") (pin "79") (pinfunction "GND65...96_79") (pintype "bidirectional"))
      (node (ref "U1") (pin "80") (pinfunction "GND65...96_80") (pintype "bidirectional"))
      (node (ref "U1") (pin "81") (pinfunction "GND65...96_81") (pintype "bidirectional"))
      (node (ref "U1") (pin "82") (pinfunction "GND65...96_82") (pintype "bidirectional"))
      (node (ref "U1") (pin "83") (pinfunction "GND65...96_83") (pintype "bidirectional"))
      (node (ref "U1") (pin "84") (pinfunction "GND65...96_84") (pintype "bidirectional"))
      (node (ref "U1") (pin "85") (pinfunction "GND65...96_85") (pintype "bidirectional"))
      (node (ref "U1") (pin "86") (pinfunction "GND65...96_86") (pintype "bidirectional"))
      (node (ref "U1") (pin "87") (pinfunction "GND65...96_87") (pintype "bidirectional"))
      (node (ref "U1") (pin "88") (pinfunction "GND65...96_88") (pintype "bidirectional"))
      (node (ref "U1") (pin "89") (pinfunction "GND65...96_89") (pintype "bidirectional"))
      (node (ref "U1") (pin "90") (pinfunction "GND65...96_90") (pintype "bidirectional"))
      (node (ref "U1") (pin "91") (pinfunction "GND65...96_91") (pintype "bidirectional"))
      (node (ref "U1") (pin "92") (pinfunction "GND65...96_92") (pintype "bidirectional"))
      (node (ref "U1") (pin "93") (pinfunction "GND65...96_93") (pintype "bidirectional"))
      (node (ref "U1") (pin "94") (pinfunction "GND65...96_94") (pintype "bidirectional"))
      (node (ref "U1") (pin "95") (pinfunction "GND65...96_95") (pintype "bidirectional"))
      (node (ref "U1") (pin "96") (pinfunction "GND65...96_96") (pintype "bidirectional"))
      (node (ref "U2") (pin "1") (pinfunction "1/OE_1") (pintype "bidirectional"))
      (node (ref "U2") (pin "10") (pinfunction "GND_10") (pintype "bidirectional"))
      (node (ref "U2") (pin "11") (pinfunction "GND_11") (pintype "bidirectional"))
      (node (ref "U2") (pin "16") (pinfunction "2/OE_16") (pintype "bidirectional"))
      (node (ref "U2") (pin "9") (pinfunction "2A2_9") (pintype "bidirectional"))
      (node (ref "U3") (pin "12") (pinfunction "VSSA_12") (pintype "power_in"))
      (node (ref "U3") (pin "18") (pinfunction "VSS_4_18") (pintype "power_in"))
      (node (ref "U3") (pin "60") (pinfunction "BOOT0_60") (pintype "bidirectional"))
      (node (ref "U3") (pin "63") (pinfunction "VSS_3_63") (pintype "power_in"))
      (node (ref "U4") (pin "1") (pinfunction "CTG_1") (pintype "bidirectional"))
      (node (ref "U4") (pin "4") (pinfunction "GND_4") (pintype "bidirectional"))
      (node (ref "U4") (pin "6") (pinfunction "QST_6") (pintype "bidirectional"))
      (node (ref "U4") (pin "EP") (pinfunction "GND_EP") (pintype "bidirectional"))
      (node (ref "U5") (pin "3") (pinfunction "GND_3") (pintype "bidirectional"))
      (node (ref "U6") (pin "3") (pinfunction "GND_3") (pintype "bidirectional"))
      (node (ref "U8") (pin "1") (pinfunction "1/OE_1") (pintype "bidirectional"))
      (node (ref "U8") (pin "10") (pinfunction "GND_10") (pintype "bidirectional"))
      (node (ref "U8") (pin "11") (pinfunction "GND_11") (pintype "bidirectional"))
      (node (ref "U8") (pin "12") (pinfunction "2B2_12") (pintype "bidirectional"))
      (node (ref "U8") (pin "16") (pinfunction "2/OE_16") (pintype "bidirectional"))
      (node (ref "U8") (pin "4") (pinfunction "1DIR_4") (pintype "bidirectional"))
      (node (ref "U8") (pin "5") (pinfunction "2DIR_5") (pintype "bidirectional"))
      (node (ref "U9") (pin "2") (pinfunction "GND_2") (pintype "passive"))
      (node (ref "X1") (pin "GND") (pinfunction "GND_GND") (pintype "bidirectional"))
      (node (ref "X1") (pin "MT1") (pinfunction "GND_MT1") (pintype "bidirectional"))
      (node (ref "X1") (pin "MT2") (pinfunction "GND_MT2") (pintype "bidirectional"))
    )
    (net (code "39") (name "ILIM") (class "Default")
      (node (ref "R2") (pin "1") (pinfunction "1_1") (pintype "passive"))
      (node (ref "U$1") (pin "10") (pinfunction "ILIM_10") (pintype "output"))
    )
    (net (code "40") (name "LED1") (class "Default")
      (node (ref "BLUE_LED_0603") (pin "A") (pinfunction "A_A") (pintype "passive"))
      (node (ref "R10") (pin "1") (pinfunction "1_1") (pintype "passive"))
    )
    (net (code "41") (name "Net-(LED2-2)") (class "Default")
      (node (ref "LED2") (pin "BLUE") (pinfunction "2_BLUE") (pintype "passive"))
      (node (ref "R11") (pin "1") (pinfunction "1_1") (pintype "passive"))
    )
    (net (code "42") (name "Net-(LED2-3)") (class "Default")
      (node (ref "LED2") (pin "GREEN") (pinfunction "3_GREEN") (pintype "passive"))
      (node (ref "R9") (pin "1") (pinfunction "1_1") (pintype "passive"))
    )
    (net (code "43") (name "Net-(LED2-4)") (class "Default")
      (node (ref "LED2") (pin "RED") (pinfunction "4_RED") (pintype "passive"))
      (node (ref "R12") (pin "1") (pinfunction "1_1") (pintype "passive"))
    )
    (net (code "44") (name "Net-(R4-Pad2)") (class "Default")
      (node (ref "R4") (pin "2") (pinfunction "2_2") (pintype "passive"))
      (node (ref "RED_LED_0603") (pin "C") (pinfunction "C_C") (pintype "passive"))
    )
    (net (code "45") (name "Net-(U$1-OTG)") (class "Default")
      (node (ref "R16") (pin "1") (pinfunction "1_1") (pintype "passive"))
      (node (ref "U$1") (pin "8") (pinfunction "OTG_8") (pintype "bidirectional"))
    )
    (net (code "46") (name "Net-(U$1-TS)") (class "Default")
      (node (ref "R18") (pin "2") (pinfunction "2_2") (pintype "passive"))
      (node (ref "R19") (pin "1") (pinfunction "1_1") (pintype "passive"))
      (node (ref "U$1") (pin "11") (pinfunction "TS_11") (pintype "bidirectional"))
      (node (ref "U$1") (pin "12") (pinfunction "~{QON}_12") (pintype "bidirectional"))
    )
    (net (code "47") (name "Net-(U3-VCAP_1)") (class "Default")
      (node (ref "C35") (pin "1") (pinfunction "1_1") (pintype "passive"))
      (node (ref "U3") (pin "31") (pinfunction "VCAP_1_31") (pintype "power_in"))
    )
    (net (code "48") (name "Net-(U3-VCAP_2)") (class "Default")
      (node (ref "C32") (pin "1") (pinfunction "1_1") (pintype "passive"))
      (node (ref "U3") (pin "47") (pinfunction "VCAP_2_47") (pintype "power_in"))
    )
    (net (code "49") (name "Net-(U4-CELL)") (class "Default")
      (node (ref "C39") (pin "1") (pinfunction "1_1") (pintype "passive"))
      (node (ref "R23") (pin "1") (pinfunction "1_1") (pintype "passive"))
      (node (ref "U4") (pin "2") (pinfunction "CELL_2") (pintype "bidirectional"))
    )
    (net (code "50") (name "Net-(U4-VDD)") (class "Default")
      (node (ref "C38") (pin "1") (pinfunction "1_1") (pintype "passive"))
      (node (ref "R22") (pin "1") (pinfunction "1_1") (pintype "passive"))
      (node (ref "U4") (pin "3") (pinfunction "VDD_3") (pintype "bidirectional"))
    )
    (net (code "51") (name "OSC32_IN_UC") (class "Default")
      (node (ref "C34") (pin "1") (pinfunction "1_1") (pintype "passive"))
      (node (ref "U3") (pin "3") (pinfunction "PC14_3") (pintype "bidirectional"))
      (node (ref "Y1") (pin "X1") (pinfunction "1_X1") (pintype "passive"))
    )
    (net (code "52") (name "OSC32_OUT_UC") (class "Default")
      (node (ref "C33") (pin "1") (pinfunction "1_1") (pintype "passive"))
      (node (ref "U3") (pin "4") (pinfunction "PC15_4") (pintype "bidirectional"))
      (node (ref "Y1") (pin "X2") (pinfunction "2_X2") (pintype "passive"))
    )
    (net (code "53") (name "OSC_IN_UC") (class "Default")
      (node (ref "C28") (pin "1") (pinfunction "1_1") (pintype "passive"))
      (node (ref "U3") (pin "5") (pinfunction "PH0/OSC_IN_5") (pintype "bidirectional"))
      (node (ref "Y2") (pin "1") (pinfunction "1_1") (pintype "passive"))
    )
    (net (code "54") (name "OSC_OUT_UC") (class "Default")
      (node (ref "C26") (pin "1") (pinfunction "1_1") (pintype "passive"))
      (node (ref "U3") (pin "6") (pinfunction "PH1/OSC_OUT_6") (pintype "bidirectional"))
      (node (ref "Y2") (pin "3") (pinfunction "2_3") (pintype "passive"))
    )
    (net (code "55") (name "PA8_PM_SCL") (class "Default")
      (node (ref "R14") (pin "1") (pinfunction "1_1") (pintype "passive"))
      (node (ref "U$1") (pin "5") (pinfunction "SCL_5") (pintype "output"))
      (node (ref "U$9") (pin "P$1") (pinfunction "TP_P$1") (pintype "bidirectional"))
      (node (ref "U3") (pin "41") (pinfunction "PA8_41") (pintype "bidirectional"))
      (node (ref "U4") (pin "7") (pinfunction "SCL_7") (pintype "bidirectional"))
    )
    (net (code "56") (name "PC9_PM_SDA") (class "Default")
      (node (ref "R13") (pin "1") (pinfunction "1_1") (pintype "passive"))
      (node (ref "U$1") (pin "6") (pinfunction "SDA_6") (pintype "bidirectional"))
      (node (ref "U$8") (pin "P$1") (pinfunction "TP_P$1") (pintype "bidirectional"))
      (node (ref "U3") (pin "40") (pinfunction "PC9_40") (pintype "bidirectional"))
      (node (ref "U4") (pin "8") (pinfunction "SDA_8") (pintype "bidirectional"))
    )
    (net (code "57") (name "PMID") (class "Default")
      (node (ref "C5") (pin "1") (pinfunction "1_1") (pintype "passive"))
      (node (ref "U$1") (pin "23") (pinfunction "PMID_23") (pintype "passive"))
    )
    (net (code "58") (name "PWR_UB") (class "Default")
      (node (ref "R1") (pin "1") (pinfunction "1_1") (pintype "passive"))
      (node (ref "U1") (pin "15") (pinfunction "PWR_ON_15") (pintype "bidirectional"))
      (node (ref "U5") (pin "4") (pinfunction "B_4") (pintype "bidirectional"))
    )
    (net (code "59") (name "PWR_UC") (class "Default")
      (node (ref "R29") (pin "1") (pinfunction "1_1") (pintype "passive"))
      (node (ref "U3") (pin "28") (pinfunction "PB2_28") (pintype "bidirectional"))
      (node (ref "U5") (pin "2") (pinfunction "A_2") (pintype "bidirectional"))
    )
    (net (code "60") (name "P_3V3") (class "Default")
      (node (ref "C18") (pin "1") (pinfunction "1_1") (pintype "passive"))
      (node (ref "C19") (pin "1") (pinfunction "1_1") (pintype "passive"))
      (node (ref "U2") (pin "3") (pinfunction "VCCA_3") (pintype "bidirectional"))
      (node (ref "U2") (pin "4") (pinfunction "1DIR_4") (pintype "bidirectional"))
      (node (ref "U2") (pin "5") (pinfunction "2DIR_5") (pintype "bidirectional"))
      (node (ref "U8") (pin "3") (pinfunction "VCCA_3") (pintype "bidirectional"))
      (node (ref "U9") (pin "1") (pinfunction "VOUT_1") (pintype "output"))
    )
    (net (code "61") (name "REGN") (class "Default")
      (node (ref "C25") (pin "1") (pinfunction "1_1") (pintype "passive"))
      (node (ref "R18") (pin "1") (pinfunction "1_1") (pintype "passive"))
      (node (ref "U$1") (pin "22") (pinfunction "REGN_22") (pintype "bidirectional"))
    )
    (net (code "62") (name "RESET_UB") (class "Default")
      (node (ref "U1") (pin "18") (pinfunction "RESET_N_18") (pintype "bidirectional"))
      (node (ref "U6") (pin "4") (pinfunction "B_4") (pintype "bidirectional"))
    )
    (net (code "63") (name "RESET_UC") (class "Default")
      (node (ref "R30") (pin "1") (pinfunction "1_1") (pintype "passive"))
      (node (ref "U3") (pin "24") (pinfunction "PC4_24") (pintype "bidirectional"))
      (node (ref "U6") (pin "2") (pinfunction "A_2") (pintype "bidirectional"))
    )
    (net (code "64") (name "RGB_BLUE") (class "Default")
      (node (ref "R11") (pin "2") (pinfunction "2_2") (pintype "passive"))
      (node (ref "U$13") (pin "P$1") (pinfunction "TP_P$1") (pintype "bidirectional"))
      (node (ref "U3") (pin "17") (pinfunction "PA3_17") (pintype "bidirectional"))
    )
    (net (code "65") (name "RGB_GREEN") (class "Default")
      (node (ref "R9") (pin "2") (pinfunction "2_2") (pintype "passive"))
      (node (ref "U$12") (pin "P$1") (pinfunction "TP_P$1") (pintype "bidirectional"))
      (node (ref "U3") (pin "16") (pinfunction "PA2_16") (pintype "bidirectional"))
    )
    (net (code "66") (name "RGB_RED") (class "Default")
      (node (ref "R12") (pin "2") (pinfunction "2_2") (pintype "passive"))
      (node (ref "U$11") (pin "P$1") (pinfunction "TP_P$1") (pintype "bidirectional"))
      (node (ref "U3") (pin "15") (pinfunction "PA1_15") (pintype "bidirectional"))
    )
    (net (code "67") (name "RI_UB") (class "Default")
      (node (ref "R28") (pin "1") (pinfunction "1_1") (pintype "passive"))
      (node (ref "U1") (pin "7") (pinfunction "RI_7") (pintype "bidirectional"))
      (node (ref "U8") (pin "14") (pinfunction "1B2_14") (pintype "bidirectional"))
    )
    (net (code "68") (name "RI_UC") (class "Default")
      (node (ref "U3") (pin "33") (pinfunction "PB12_33") (pintype "bidirectional"))
      (node (ref "U8") (pin "7") (pinfunction "1A2_7") (pintype "bidirectional"))
    )
    (net (code "69") (name "RTS_UB") (class "Default")
      (node (ref "U1") (pin "10") (pinfunction "RTS_10") (pintype "bidirectional"))
      (node (ref "U2") (pin "15") (pinfunction "1B1_15") (pintype "bidirectional"))
    )
    (net (code "70") (name "RTS_UC") (class "Default")
      (node (ref "R24") (pin "1") (pinfunction "1_1") (pintype "passive"))
      (node (ref "U2") (pin "6") (pinfunction "1A1_6") (pintype "bidirectional"))
      (node (ref "U3") (pin "35") (pinfunction "PB14_35") (pintype "bidirectional"))
    )
    (net (code "71") (name "RX") (class "Default")
      (node (ref "JP1") (pin "4") (pinfunction "4_4") (pintype "passive"))
      (node (ref "U3") (pin "43") (pinfunction "PA10_43") (pintype "bidirectional"))
    )
    (net (code "72") (name "RXD_UB") (class "Default")
      (node (ref "R21") (pin "1") (pinfunction "1_1") (pintype "passive"))
      (node (ref "U1") (pin "13") (pinfunction "RXD_13") (pintype "bidirectional"))
      (node (ref "U8") (pin "13") (pinfunction "2B1_13") (pintype "bidirectional"))
    )
    (net (code "73") (name "RXD_UC") (class "Default")
      (node (ref "U3") (pin "30") (pinfunction "PB11_30") (pintype "bidirectional"))
      (node (ref "U8") (pin "8") (pinfunction "2A1_8") (pintype "bidirectional"))
    )
    (net (code "74") (name "SIM_CLK") (class "Default")
      (node (ref "C12") (pin "1") (pinfunction "1_1") (pintype "passive"))
      (node (ref "J1") (pin "C3") (pinfunction "CLK_C3") (pintype "passive"))
      (node (ref "U1") (pin "38") (pinfunction "SIM_CLK_38") (pintype "bidirectional"))
    )
    (net (code "75") (name "SIM_DET") (class "Default")
      (node (ref "U1") (pin "42") (pinfunction "SIM_DET_42") (pintype "bidirectional"))
    )
    (net (code "76") (name "SIM_IO") (class "Default")
      (node (ref "C13") (pin "1") (pinfunction "1_1") (pintype "passive"))
      (node (ref "J1") (pin "C7") (pinfunction "I/O_C7") (pintype "passive"))
      (node (ref "U1") (pin "39") (pinfunction "SIM_IO_39") (pintype "bidirectional"))
    )
    (net (code "77") (name "SIM_RST") (class "Default")
      (node (ref "C10") (pin "1") (pinfunction "1_1") (pintype "passive"))
      (node (ref "J1") (pin "C2") (pinfunction "RST_C2") (pintype "passive"))
      (node (ref "U1") (pin "40") (pinfunction "SIM_RST_40") (pintype "bidirectional"))
    )
    (net (code "78") (name "SIM_VCC") (class "Default")
      (node (ref "C11") (pin "1") (pinfunction "1_1") (pintype "passive"))
      (node (ref "C14") (pin "1") (pinfunction "1_1") (pintype "passive"))
      (node (ref "J1") (pin "C1") (pinfunction "VCC_C1") (pintype "passive"))
      (node (ref "J1") (pin "C6") (pinfunction "VPP_C6") (pintype "passive"))
      (node (ref "U1") (pin "41") (pinfunction "VSIM_41") (pintype "bidirectional"))
    )
    (net (code "79") (name "STAT") (class "Default")
      (node (ref "R4") (pin "1") (pinfunction "1_1") (pintype "passive"))
      (node (ref "U$1") (pin "4") (pinfunction "STAT_4") (pintype "bidirectional"))
    )
    (net (code "80") (name "SW1") (class "Default")
      (node (ref "C7") (pin "2") (pinfunction "2_2") (pintype "passive"))
      (node (ref "U$1") (pin "19") (pinfunction "SW_19") (pintype "power_in"))
      (node (ref "U$1") (pin "20") (pinfunction "SW_20") (pintype "power_in"))
      (node (ref "U$4") (pin "P$1") (pinfunction "1_P$1") (pintype "passive"))
    )
    (net (code "81") (name "SW2") (class "Default")
      (node (ref "U$5") (pin "P$1") (pinfunction "P$1_P$1") (pintype "bidirectional"))
      (node (ref "U$6") (pin "1") (pinfunction "1_1") (pintype "passive"))
    )
    (net (code "82") (name "TX") (class "Default")
      (node (ref "JP1") (pin "3") (pinfunction "3_3") (pintype "passive"))
      (node (ref "U3") (pin "42") (pinfunction "PA9_42") (pintype "bidirectional"))
    )
    (net (code "83") (name "TXD_UB") (class "Default")
      (node (ref "U1") (pin "12") (pinfunction "TXD_12") (pintype "bidirectional"))
      (node (ref "U2") (pin "14") (pinfunction "1B2_14") (pintype "bidirectional"))
    )
    (net (code "84") (name "TXD_UC") (class "Default")
      (node (ref "R25") (pin "1") (pinfunction "1_1") (pintype "passive"))
      (node (ref "U2") (pin "7") (pinfunction "1A2_7") (pintype "bidirectional"))
      (node (ref "U3") (pin "29") (pinfunction "PB10_29") (pintype "bidirectional"))
    )
    (net (code "85") (name "USB_DM") (class "Default")
      (node (ref "R6") (pin "2") (pinfunction "2_2") (pintype "passive"))
      (node (ref "U$1") (pin "3") (pinfunction "~{PG}_3") (pintype "output"))
      (node (ref "U$7") (pin "P$2") (pinfunction "P$2_P$2") (pintype "bidirectional"))
      (node (ref "X1") (pin "D-") (pinfunction "D-_D-") (pintype "bidirectional"))
    )
    (net (code "86") (name "USB_DM_UC") (class "Default")
      (node (ref "R6") (pin "1") (pinfunction "1_1") (pintype "passive"))
      (node (ref "U3") (pin "44") (pinfunction "PA11_44") (pintype "bidirectional"))
    )
    (net (code "87") (name "USB_DP") (class "Default")
      (node (ref "R5") (pin "2") (pinfunction "2_2") (pintype "passive"))
      (node (ref "U$1") (pin "2") (pinfunction "PSEL_2") (pintype "output"))
      (node (ref "U$7") (pin "P$1") (pinfunction "P$1_P$1") (pintype "bidirectional"))
      (node (ref "X1") (pin "D+") (pinfunction "D+_D+") (pintype "bidirectional"))
    )
    (net (code "88") (name "USB_DP_UC") (class "Default")
      (node (ref "R5") (pin "1") (pinfunction "1_1") (pintype "passive"))
      (node (ref "U3") (pin "45") (pinfunction "PA12_45") (pintype "bidirectional"))
    )
    (net (code "89") (name "VBAT") (class "Default")
      (node (ref "J3") (pin "2") (pinfunction "2_2") (pintype "bidirectional"))
      (node (ref "JP2") (pin "16") (pinfunction "16_16") (pintype "passive"))
      (node (ref "U3") (pin "1") (pinfunction "VBAT_1") (pintype "power_in"))
    )
    (net (code "90") (name "VBUS") (class "Default")
      (node (ref "JP3") (pin "1") (pinfunction "1_1") (pintype "passive"))
      (node (ref "U$3") (pin "ANODE") (pinfunction "ANODE_ANODE") (pintype "bidirectional"))
      (node (ref "X1") (pin "VBUS") (pinfunction "VBUS_VBUS") (pintype "bidirectional"))
    )
    (net (code "91") (name "VIN") (class "Default")
      (node (ref "C4") (pin "1") (pinfunction "1_1") (pintype "passive"))
      (node (ref "JP1") (pin "1") (pinfunction "1_1") (pintype "passive"))
      (node (ref "U$1") (pin "1") (pinfunction "VBUS_1") (pintype "power_in"))
      (node (ref "U$1") (pin "24") (pinfunction "VBUS_24") (pintype "passive"))
      (node (ref "U$3") (pin "CATHODE") (pinfunction "CATHODE_CATHODE") (pintype "bidirectional"))
    )
    (net (code "92") (name "V_BCKP") (class "Default")
      (node (ref "R1") (pin "2") (pinfunction "2_2") (pintype "passive"))
      (node (ref "U1") (pin "2") (pinfunction "V_BCKP_2") (pintype "bidirectional"))
    )
    (net (code "93") (name "V_INT") (class "Default")
      (node (ref "C21") (pin "1") (pinfunction "1_1") (pintype "passive"))
      (node (ref "C22") (pin "1") (pinfunction "1_1") (pintype "passive"))
      (node (ref "R3") (pin "2") (pinfunction "2_2") (pintype "passive"))
      (node (ref "U1") (pin "4") (pinfunction "V_INT_4") (pintype "bidirectional"))
      (node (ref "U2") (pin "2") (pinfunction "VCCB_2") (pintype "bidirectional"))
      (node (ref "U8") (pin "2") (pinfunction "VCCB_2") (pintype "bidirectional"))
    )
    (net (code "94") (name "WKP") (class "Default")
      (node (ref "JP1") (pin "5") (pinfunction "5_5") (pintype "passive"))
      (node (ref "U3") (pin "14") (pinfunction "WKUP/PA0_14") (pintype "bidirectional"))
    )
    (net (code "95") (name "unconnected-(RESET-Pad1)") (class "Default")
      (node (ref "RESET") (pin "1") (pinfunction "1_1") (pintype "passive"))
    )
    (net (code "96") (name "unconnected-(SETUP-Pad4)") (class "Default")
      (node (ref "SETUP") (pin "4") (pinfunction "4_4") (pintype "passive"))
    )
    (net (code "97") (name "unconnected-(U1-DCD-Pad8)") (class "Default")
      (node (ref "U1") (pin "8") (pinfunction "DCD_8") (pintype "bidirectional"))
    )
    (net (code "98") (name "unconnected-(U1-DSR-Pad6)") (class "Default")
      (node (ref "U1") (pin "6") (pinfunction "DSR_6") (pintype "bidirectional"))
    )
    (net (code "99") (name "unconnected-(U1-GPIO1-Pad16)") (class "Default")
      (node (ref "U1") (pin "16") (pinfunction "GPIO1_16") (pintype "bidirectional"))
    )
    (net (code "100") (name "unconnected-(U1-GPIO2-Pad23)") (class "Default")
      (node (ref "U1") (pin "23") (pinfunction "GPIO2_23") (pintype "bidirectional"))
    )
    (net (code "101") (name "unconnected-(U1-GPIO3-Pad24)") (class "Default")
      (node (ref "U1") (pin "24") (pinfunction "GPIO3_24") (pintype "bidirectional"))
    )
    (net (code "102") (name "unconnected-(U1-GPIO4-Pad25)") (class "Default")
      (node (ref "U1") (pin "25") (pinfunction "GPIO4_25") (pintype "bidirectional"))
    )
    (net (code "103") (name "unconnected-(U1-I2S_CLK-Pad36)") (class "Default")
      (node (ref "U1") (pin "36") (pinfunction "I2S_CLK_36") (pintype "bidirectional"))
    )
    (net (code "104") (name "unconnected-(U1-I2S_RXD-Pad37)") (class "Default")
      (node (ref "U1") (pin "37") (pinfunction "I2S_RXD_37") (pintype "bidirectional"))
    )
    (net (code "105") (name "unconnected-(U1-I2S_TXD-Pad35)") (class "Default")
      (node (ref "U1") (pin "35") (pinfunction "I2S_TXD_35") (pintype "bidirectional"))
    )
    (net (code "106") (name "unconnected-(U1-I2S_WA-Pad34)") (class "Default")
      (node (ref "U1") (pin "34") (pinfunction "I2S_WA_34") (pintype "bidirectional"))
    )
    (net (code "107") (name "unconnected-(U1-MIC_BIAS-Pad46)") (class "Default")
      (node (ref "U1") (pin "46") (pinfunction "MIC_BIAS_46") (pintype "bidirectional"))
    )
    (net (code "108") (name "unconnected-(U1-MIC_GND-Pad47)") (class "Default")
      (node (ref "U1") (pin "47") (pinfunction "MIC_GND_47") (pintype "bidirectional"))
    )
    (net (code "109") (name "unconnected-(U1-MIC_N-Pad48)") (class "Default")
      (node (ref "U1") (pin "48") (pinfunction "MIC_N_48") (pintype "bidirectional"))
    )
    (net (code "110") (name "unconnected-(U1-MIC_P-Pad49)") (class "Default")
      (node (ref "U1") (pin "49") (pinfunction "MIC_P_49") (pintype "bidirectional"))
    )
    (net (code "111") (name "unconnected-(U1-RSVD-Pad19)") (class "Default")
      (node (ref "U1") (pin "19") (pinfunction "RSVD_19") (pintype "bidirectional"))
    )
    (net (code "112") (name "unconnected-(U1-RSVD-Pad31)") (class "Default")
      (node (ref "U1") (pin "31") (pinfunction "RSVD_31") (pintype "bidirectional"))
    )
    (net (code "113") (name "unconnected-(U1-RXD_AUX{slash}USB_D--Pad28)") (class "Default")
      (node (ref "U1") (pin "28") (pinfunction "RXD_AUX/USB_D-_28") (pintype "bidirectional"))
    )
    (net (code "114") (name "unconnected-(U1-SCL-Pad27)") (class "Default")
      (node (ref "U1") (pin "27") (pinfunction "SCL_27") (pintype "bidirectional"))
    )
    (net (code "115") (name "unconnected-(U1-SDA-Pad26)") (class "Default")
      (node (ref "U1") (pin "26") (pinfunction "SDA_26") (pintype "bidirectional"))
    )
    (net (code "116") (name "unconnected-(U1-SPK_N-Pad45)") (class "Default")
      (node (ref "U1") (pin "45") (pinfunction "SPK_N_45") (pintype "bidirectional"))
    )
    (net (code "117") (name "unconnected-(U1-SPK_P-Pad44)") (class "Default")
      (node (ref "U1") (pin "44") (pinfunction "SPK_P_44") (pintype "bidirectional"))
    )
    (net (code "118") (name "unconnected-(U1-TXD_AUX{slash}USB_D+-Pad29)") (class "Default")
      (node (ref "U1") (pin "29") (pinfunction "TXD_AUX/USB_D+_29") (pintype "bidirectional"))
    )
    (net (code "119") (name "unconnected-(U1-VUSB_DET-Pad17)") (class "Default")
      (node (ref "U1") (pin "17") (pinfunction "VUSB_DET_17") (pintype "bidirectional"))
    )
    (net (code "120") (name "unconnected-(U2-2B2-Pad12)") (class "Default")
      (node (ref "U2") (pin "12") (pinfunction "2B2_12") (pintype "bidirectional"))
    )
    (net (code "121") (name "unconnected-(U8-2A2-Pad9)") (class "Default")
      (node (ref "U8") (pin "9") (pinfunction "2A2_9") (pintype "bidirectional"))
    )
    (net (code "122") (name "unconnected-(U9-OC-Pad3)") (class "Default")
      (node (ref "U9") (pin "3") (pinfunction "OC_3") (pintype "output"))
    )
    (net (code "123") (name "~{BATT_INT_PC13}") (class "Default")
      (node (ref "R15") (pin "1") (pinfunction "1_1") (pintype "passive"))
      (node (ref "U$1") (pin "7") (pinfunction "INT_7") (pintype "bidirectional"))
      (node (ref "U3") (pin "2") (pinfunction "PC13_2") (pintype "bidirectional"))
      (node (ref "U4") (pin "5") (pinfunction "ALT_5") (pintype "bidirectional"))
    )
    (net (code "124") (name "~{CE}") (class "Default")
      (node (ref "R17") (pin "1") (pinfunction "1_1") (pintype "passive"))
      (node (ref "U$1") (pin "9") (pinfunction "~{CE}_9") (pintype "output"))
    )
    (net (code "125") (name "~{RST}") (class "Default")
      (node (ref "C6") (pin "1") (pinfunction "1_1") (pintype "passive"))
      (node (ref "JP2") (pin "17") (pinfunction "17_17") (pintype "passive"))
      (node (ref "R8") (pin "1") (pinfunction "1_1") (pintype "passive"))
      (node (ref "RESET") (pin "2") (pinfunction "2_2") (pintype "passive"))
      (node (ref "U3") (pin "7") (pinfunction "NRST_7") (pintype "power_in"))
    )
    (net (code "126") (name "~{SETUP}") (class "Default")
      (node (ref "SETUP") (pin "3") (pinfunction "3_3") (pintype "passive"))
      (node (ref "U3") (pin "38") (pinfunction "PC7_38") (pintype "bidirectional"))
    )
  )
)
